# LacewingPXE_v3p1.net
KiCad netlist of a schematic drawn in Altium Designer
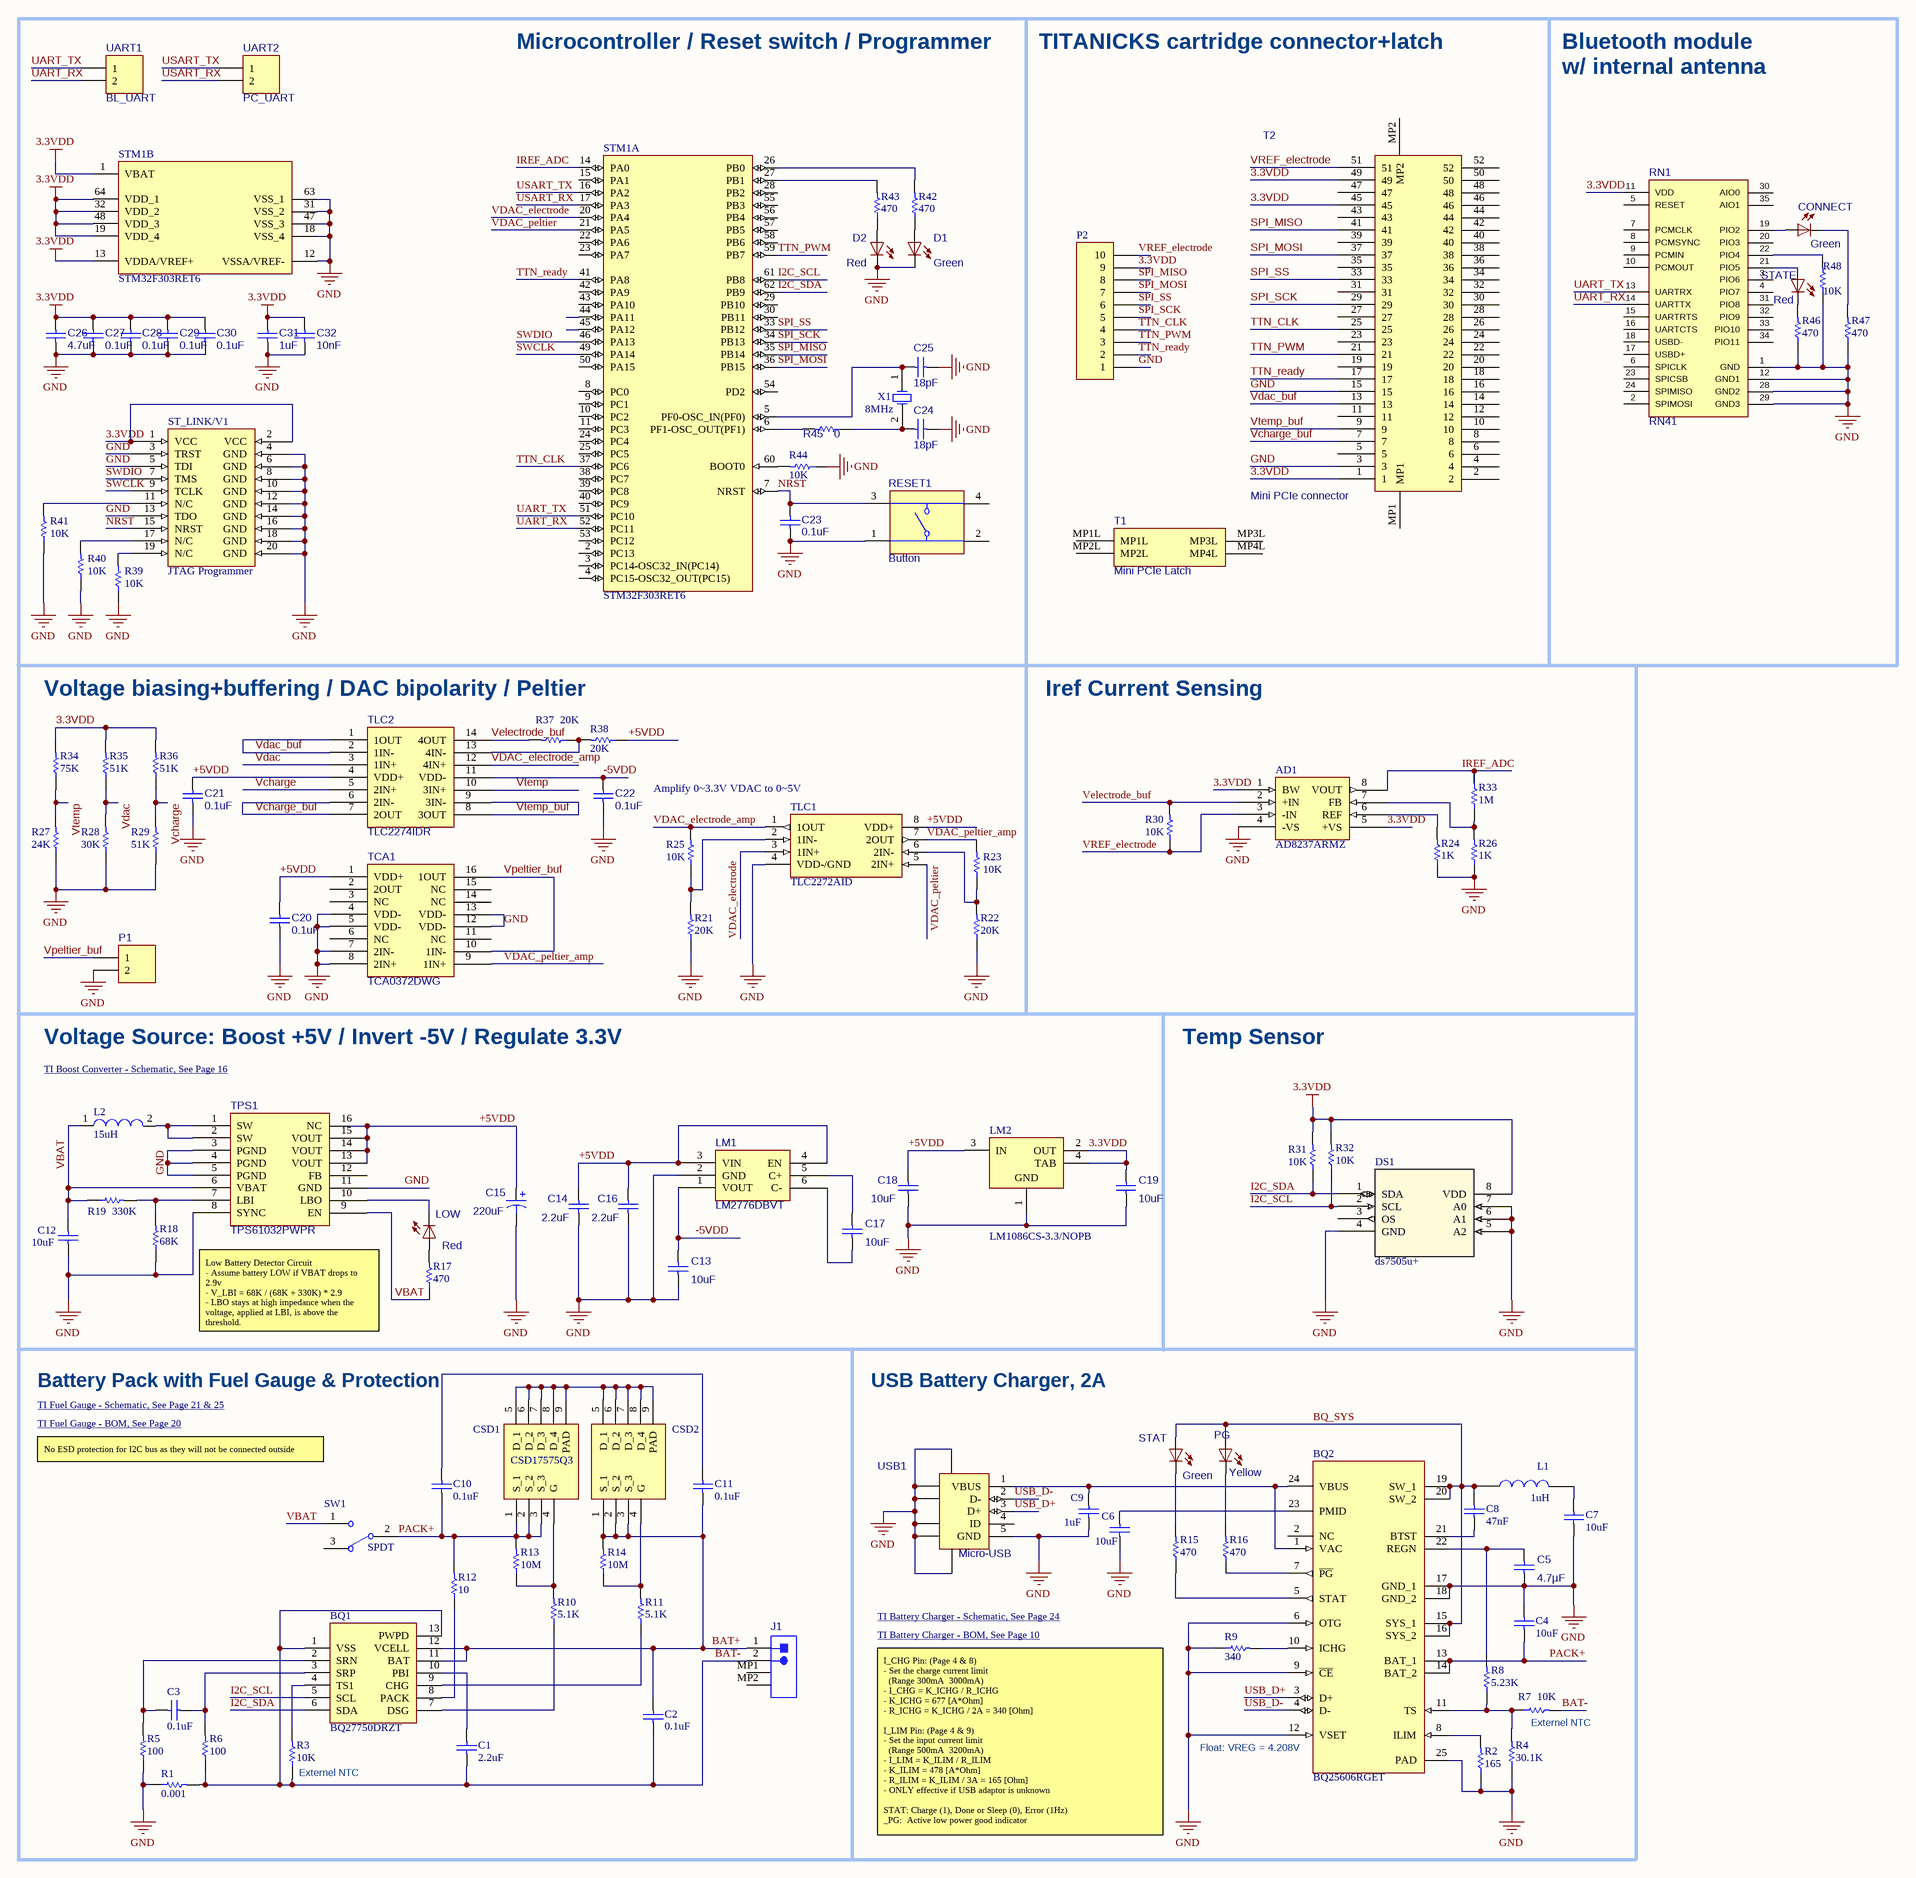
[diagram p0: LacewingPXE_v3p1.SchDoc]

(export (version "E")
  (design (tool "Eeschema 10.0.6"))
  (components
    (comp (ref "AD1")
      (value "AD8237ARMZ")
      (footprint "ADI-RM-8_N")
      (description "Instrument Amplifier")
      (fields (field (name "MANUFACTURER") "ANALOG DEVICES"))
      (libsource (lib "Device_mbd_v1") (part "AD8237"))
    )
    (comp (ref "BQ1")
      (value "BQ27750DRZT")
      (footprint "BQ27510DRZT")
      (description "Fuel Gauge and Protection")
      (fields (field (name "MANUFACTURER") "TEXAS INSTRUMENTS"))
      (libsource (lib "*") (part "BQ27750DRZT"))
    )
    (comp (ref "BQ2")
      (value "BQ25606RGET")
      (footprint "SamacSys:QFN50P400X400X100-25N")
      (description "Battery Charger")
      (fields (field (name "MANUFACTURER") "TEXAS INSTRUMENTS"))
      (libsource (lib "*") (part "BQ25606RGET"))
    )
    (comp (ref "C1")
      (value "2.2uF")
      (footprint "CAPC1005X55X25NL05T10")
      (description "CAP 0402")
      (fields (field (name "MANUFACTURER") "MURATA") (field (name "PART NO") "GRM155R60J225ME15D"))
      (libsource (lib "Altium Content Vault") (part "CAP-NP-2"))
    )
    (comp (ref "C2")
      (value "0.1uF")
      (footprint "CAPC1005X56X25LL10T15")
      (description "CAP 0402")
      (fields (field (name "MANUFACTURER") "AVX") (field (name "PART NO") "04026D104KAT2A"))
      (libsource (lib "Altium Content Vault") (part "CAP"))
    )
    (comp (ref "C3")
      (value "0.1uF")
      (footprint "CAPC1005X56X25LL10T15")
      (description "CAP 0402")
      (fields (field (name "MANUFACTURER") "AVX") (field (name "PART NO") "04026D104KAT2A"))
      (libsource (lib "Altium Content Vault") (part "CAP"))
    )
    (comp (ref "C4")
      (value "10uF")
      (footprint "CAPC2013X140X50ML20T25")
      (description "CAP 0805")
      (fields (field (name "MANUFACTURER") "AVX") (field (name "PART NO") "0805ZC106KAT2A"))
      (libsource (lib "Altium Content Vault") (part "CAP"))
    )
    (comp (ref "C5")
      (value "4.7µF")
      (footprint "CAPC0603(1608)100_N")
      (description "CAP 0603")
      (fields (field (name "MANUFACTURER") "MURATA") (field (name "PART NO") "GRM188R61C475KAAJD"))
      (libsource (lib "altium-import") (part "root_1_CAP_"))
    )
    (comp (ref "C6")
      (value "10uF")
      (footprint "CAPC2013X95X45NL10T25")
      (description "CAP 0805")
      (fields (field (name "MANUFACTURER") "MURATA") (field (name "PART NO") "GRM21BC71E106KE11L"))
      (libsource (lib "Altium Content Vault") (part "CAP"))
    )
    (comp (ref "C7")
      (value "10uF")
      (footprint "CAPC2013X140X50ML20T25")
      (description "CAP 0805")
      (fields (field (name "MANUFACTURER") "AVX") (field (name "PART NO") "0805ZC106KAT2A"))
      (libsource (lib "Altium Content Vault") (part "CAP"))
    )
    (comp (ref "C8")
      (value "47nF")
      (footprint "CAPC1005X55X25NL05T10")
      (description "CAP 0402")
      (fields (field (name "MANUFACTURER") "AVX") (field (name "PART NO") "0402YD473KAT2A"))
      (libsource (lib "Altium Content Vault") (part "CAP-NP-2"))
    )
    (comp (ref "C9")
      (value "1uF")
      (footprint "CAPC2013X95X45NL10T25")
      (description "CAP 0805")
      (fields (field (name "MANUFACTURER") "AVX") (field (name "PART NO") "08053C105JAT2A"))
      (libsource (lib "Altium Content Vault") (part "CAP"))
    )
    (comp (ref "C10")
      (value "0.1uF")
      (footprint "CAPC1005X56X25LL10T15")
      (description "CAP 0402")
      (fields (field (name "MANUFACTURER") "AVX") (field (name "PART NO") "04026D104KAT2A"))
      (libsource (lib "Altium Content Vault") (part "CAP"))
    )
    (comp (ref "C11")
      (value "0.1uF")
      (footprint "CAPC1005X56X25LL10T15")
      (description "CAP 0402")
      (fields (field (name "MANUFACTURER") "AVX") (field (name "PART NO") "04026D104KAT2A"))
      (libsource (lib "Altium Content Vault") (part "CAP"))
    )
    (comp (ref "C12")
      (value "10uF")
      (footprint "CAPC2013X140X50NL20T25")
      (description "CAP 0805")
      (fields (field (name "MANUFACTURER") "AVX") (field (name "PART NO") "08056D106KAT2A"))
      (libsource (lib "Altium Content Vault") (part "CAP"))
    )
    (comp (ref "C13")
      (value "10uF")
      (footprint "CAPC0805(2012)75_N")
      (description "CAP 0805")
      (fields (field (name "MANUFACTURER") "WURTH ELEKTRONIK") (field (name "PART NO") "885012107010"))
      (libsource (lib "Altium Content Vault") (part "CMP-1036-00002-1"))
    )
    (comp (ref "C14")
      (value "2.2uF")
      (footprint "CAPC0805(2012)75_N")
      (description "CAP 0805")
      (fields (field (name "MANUFACTURER") "MULTICOMP") (field (name "PART NO") "MC0805B225K250CT"))
      (libsource (lib "Altium Content Vault") (part "CMP-1036-00002-1"))
    )
    (comp (ref "C15")
      (value "220uF")
      (footprint "AVX-CAPC7343_V")
      (description "CAP 2917")
      (fields (field (name "MANUFACTURER") "AVX") (field (name "PART NO") "TAJD227K010RNJ"))
      (libsource (lib "Altium Content Vault") (part "CMP-0279-00002-1"))
    )
    (comp (ref "C16")
      (value "2.2uF")
      (footprint "CAPC0805(2012)75_N")
      (description "CAP 0805")
      (fields (field (name "MANUFACTURER") "MULTICOMP") (field (name "PART NO") "MC0805B225K250CT"))
      (libsource (lib "Altium Content Vault") (part "CMP-1036-00002-1"))
    )
    (comp (ref "C17")
      (value "10uF")
      (footprint "CAPC0805(2012)75_N")
      (description "CAP 0805")
      (fields (field (name "MANUFACTURER") "WURTH ELEKTRONIK") (field (name "PART NO") "885012107010"))
      (libsource (lib "Altium Content Vault") (part "CMP-1036-00002-1"))
    )
    (comp (ref "C18")
      (value "10uF")
      (footprint "CAPC0805(2012)75_N")
      (description "CAP 0805")
      (fields (field (name "MANUFACTURER") "WURTH ELEKTRONIK") (field (name "PART NO") "885012107010"))
      (libsource (lib "Altium Content Vault") (part "CMP-1036-00002-1"))
    )
    (comp (ref "C19")
      (value "10uF")
      (footprint "CAPC0805(2012)75_N")
      (description "CAP 0805")
      (fields (field (name "MANUFACTURER") "WURTH ELEKTRONIK") (field (name "PART NO") "885012107010"))
      (libsource (lib "Altium Content Vault") (part "CMP-1036-00002-1"))
    )
    (comp (ref "C20")
      (value "0.1uF")
      (footprint "CAPC0603(1608)100_N")
      (description "CAP 0603")
      (fields (field (name "MANUFACTURER") "MULTICOMP") (field (name "PART NO") "MC0603B104K500CT"))
      (libsource (lib "Altium Content Vault") (part "CAP"))
    )
    (comp (ref "C21")
      (value "0.1uF")
      (footprint "CAPC0603(1608)100_N")
      (description "CAP 0603")
      (fields (field (name "MANUFACTURER") "MULTICOMP") (field (name "PART NO") "MC0603B104K500CT"))
      (libsource (lib "Altium Content Vault") (part "CAP"))
    )
    (comp (ref "C22")
      (value "0.1uF")
      (footprint "CAPC0603(1608)100_N")
      (description "CAP 0603")
      (fields (field (name "MANUFACTURER") "MULTICOMP") (field (name "PART NO") "MC0603B104K500CT"))
      (libsource (lib "Altium Content Vault") (part "CAP"))
    )
    (comp (ref "C23")
      (value "0.1uF")
      (footprint "CAPC0603(1608)100_N")
      (description "CAP 0603")
      (fields (field (name "MANUFACTURER") "MULTICOMP") (field (name "PART NO") "MC0603B104K500CT"))
      (libsource (lib "Altium Content Vault") (part "CAP"))
    )
    (comp (ref "C24")
      (value "18pF")
      (footprint "CAPC0603(1608)100_N")
      (description "CAP 0603")
      (fields (field (name "MANUFACTURER") "KEMET") (field (name "PART NO") "C0603C180K5RACTU"))
      (libsource (lib "Altium Content Vault") (part "CAP"))
    )
    (comp (ref "C25")
      (value "18pF")
      (footprint "CAPC0603(1608)100_N")
      (description "CAP 0603")
      (fields (field (name "MANUFACTURER") "KEMET") (field (name "PART NO") "C0603C180K5RACTU"))
      (libsource (lib "Altium Content Vault") (part "CAP"))
    )
    (comp (ref "C26")
      (value "4.7uF")
      (footprint "CAPC0603(1608)100_N")
      (description "CAP 0603")
      (fields (field (name "MANUFACTURER") "AVX") (field (name "PART NO") "06036D475KAT2A"))
      (libsource (lib "Altium Content Vault") (part "CAP"))
    )
    (comp (ref "C27")
      (value "0.1uF")
      (footprint "CAPC0603(1608)100_N")
      (description "CAP 0603")
      (fields (field (name "MANUFACTURER") "MULTICOMP") (field (name "PART NO") "MC0603B104K500CT"))
      (libsource (lib "Altium Content Vault") (part "CAP"))
    )
    (comp (ref "C28")
      (value "0.1uF")
      (footprint "CAPC0603(1608)100_N")
      (description "CAP 0603")
      (fields (field (name "MANUFACTURER") "MULTICOMP") (field (name "PART NO") "MC0603B104K500CT"))
      (libsource (lib "Altium Content Vault") (part "CAP"))
    )
    (comp (ref "C29")
      (value "0.1uF")
      (footprint "CAPC0603(1608)100_N")
      (description "CAP 0603")
      (fields (field (name "MANUFACTURER") "MULTICOMP") (field (name "PART NO") "MC0603B104K500CT"))
      (libsource (lib "Altium Content Vault") (part "CAP"))
    )
    (comp (ref "C30")
      (value "0.1uF")
      (footprint "CAPC0603(1608)100_N")
      (description "CAP 0603")
      (fields (field (name "MANUFACTURER") "MULTICOMP") (field (name "PART NO") "MC0603B104K500CT"))
      (libsource (lib "Altium Content Vault") (part "CAP"))
    )
    (comp (ref "C31")
      (value "1uF")
      (footprint "CAPC0603(1608)100_N")
      (description "CAP 0603")
      (fields (field (name "MANUFACTURER") "AVX") (field (name "PART NO") "06033D105KAT2A"))
      (libsource (lib "Altium Content Vault") (part "CAP"))
    )
    (comp (ref "C32")
      (value "10nF")
      (footprint "CAPC0603(1608)100_N")
      (description "CAP 0603")
      (fields (field (name "MANUFACTURER") "KEMET") (field (name "PART NO") "C0603C103K5RAC7081"))
      (libsource (lib "Altium Content Vault") (part "CAP"))
    )
    (comp (ref "CONNECT")
      (value "Green")
      (footprint "LED-0603")
      (description "LED SMD 0603")
      (fields (field (name "MANUFACTURER") "KINGBRIGHT") (field (name "PART NO") "KPT-1608SGC"))
      (libsource (lib "TTN_chip") (part "LED0603"))
    )
    (comp (ref "CSD1")
      (value "CSD17575Q3")
      (footprint "SamacSys:CSD16327")
      (description "MOSFET")
      (fields (field (name "MANUFACTURER") "TEXAS INSTRUMENTS") (field (name "PART NO") "CSD17575Q3T"))
      (libsource (lib "*") (part "CSD17575Q3"))
    )
    (comp (ref "CSD2")
      (value "CSD17575Q3")
      (footprint "SamacSys:CSD16327")
      (description "MOSFET")
      (fields (field (name "MANUFACTURER") "TEXAS INSTRUMENTS") (field (name "PART NO") "CSD17575Q3T"))
      (libsource (lib "*") (part "CSD17575Q3"))
    )
    (comp (ref "D1")
      (value "Green")
      (footprint "LED-0603")
      (description "LED SMD 0603")
      (fields (field (name "MANUFACTURER") "KINGBRIGHT") (field (name "PART NO") "KPT-1608SGC"))
      (libsource (lib "TTN_chip") (part "LED0603"))
    )
    (comp (ref "D2")
      (value "Red")
      (footprint "LED-0603")
      (description "LED SMD 0603")
      (fields (field (name "MANUFACTURER") "KINGBRIGHT") (field (name "PART NO") "KPT-1608SECK-J3"))
      (libsource (lib "TTN_chip") (part "LED0603"))
    )
    (comp (ref "DS1")
      (value "ds7505u+")
      (footprint "21-0036K")
      (description "Digital Thermometer")
      (fields (field (name "MANUFACTURER") "MAXIM") (field (name "PART NO") "DS7505U+"))
      (libsource (lib "2019-05-15_15-51-07") (part "ds7505u+"))
    )
    (comp (ref "J1")
      (value "~")
      (footprint "JST- S2B-PH-SM4-TB(LF)(SN)-2_V")
      (description "Battery Connector")
      (fields (field (name "MANUFACTURER") "JST") (field (name "PART NO") "S2B-PH-SM4-TB(LF)(SN)"))
      (libsource (lib "Altium Content Vault") (part "SYM-0368-00001-1"))
    )
    (comp (ref "L1")
      (value "1uH")
      (footprint "INDC2520X120N")
      (description "Inductor")
      (fields (field (name "MANUFACTURER") "MURATA") (field (name "PART NO") "DFE252012F-1R0M=P2"))
      (libsource (lib "*") (part "DFE252012F-1R0M=P2"))
    )
    (comp (ref "L2")
      (value "15uH")
      (footprint "WE-PD 1050")
      (description "Power Inductor")
      (fields (field (name "MANUFACTURER") "WURTH ELEKTRONIK") (field (name "PART NO") "7447714150"))
      (libsource (lib "Altium Content Vault") (part "PAS-IND-INDUCTOR-2"))
    )
    (comp (ref "LM1")
      (value "LM2776DBVT")
      (footprint "TI-DBV6_M")
      (description "Voltage Inverter -5V")
      (fields (field (name "MANUFACTURER") "TEXAS INSTRUMENTS"))
      (libsource (lib "Device_mbd_v1") (part "LM2776"))
    )
    (comp (ref "LM2")
      (value "LM1086CS-3.3/NOPB")
      (footprint "KTT0003B_N")
      (description "1.5A 3.3V LDO")
      (fields (field (name "MANUFACTURER") "TEXAS INSTRUMENTS"))
      (libsource (lib "Altium Content Vault") (part "PM-REG-LM1086-SOT4"))
    )
    (comp (ref "LOW")
      (value "Red")
      (footprint "LED-0603")
      (description "LED SMD 0603")
      (fields (field (name "MANUFACTURER") "KINGBRIGHT") (field (name "PART NO") "KPT-1608SECK-J3"))
      (libsource (lib "TTN_chip") (part "LED0603"))
    )
    (comp (ref "P1")
      (value "~")
      (footprint "HDR1X2")
      (description "Header, 2-Pin")
      (libsource (lib "Miscellaneous Connectors") (part "Header 2"))
    )
    (comp (ref "P2")
      (value "~")
      (footprint "HDR1X10")
      (description "Header, 10-Pin")
      (libsource (lib "Miscellaneous Connectors") (part "Header 10"))
    )
    (comp (ref "PG")
      (value "Yellow")
      (footprint "LED-0603")
      (description "LED SMD 0603")
      (fields (field (name "MANUFACTURER") "KINGBRIGHT") (field (name "PART NO") "KPT-1608SYCK-J3"))
      (libsource (lib "TTN_chip") (part "LED0603"))
    )
    (comp (ref "R1")
      (value "0.001")
      (footprint "RESC3216X89X104LL25T25")
      (description "RES 1206")
      (fields (field (name "MANUFACTURER") "VISHAY") (field (name "PART NO") "WSLP12061L000FEA"))
      (libsource (lib "Altium Content Vault") (part "RES-2"))
    )
    (comp (ref "R2")
      (value "165")
      (footprint "RESC1005X40X25NL05T05")
      (description "RES 0402")
      (fields (field (name "MANUFACTURER") "VISHAY") (field (name "PART NO") "CRCW0402165RFKED"))
      (libsource (lib "Altium Content Vault") (part "RES"))
    )
    (comp (ref "R3")
      (value "10K")
      (footprint "RESC1005X40X25LL05T05")
      (description "Thermistor RES 0402")
      (fields (field (name "MANUFACTURER") "PANASONIC") (field (name "PART NO") "ERTJ0EG103FA"))
      (libsource (lib "Altium Content Vault") (part "RES"))
    )
    (comp (ref "R4")
      (value "30.1K")
      (footprint "RESC1005X40X25LL05T05")
      (description "RES 0402")
      (fields (field (name "MANUFACTURER") "VISHAY") (field (name "PART NO") "CRCW040230K1FKED"))
      (libsource (lib "Altium Content Vault") (part "RES-2"))
    )
    (comp (ref "R5")
      (value "100")
      (footprint "RESC1005X40X25NL05T05")
      (description "RES 0402")
      (fields (field (name "MANUFACTURER") "VISHAY") (field (name "PART NO") "CRCW0402100RFKED"))
      (libsource (lib "Altium Content Vault") (part "RES"))
    )
    (comp (ref "R6")
      (value "100")
      (footprint "RESC1005X40X25NL05T05")
      (description "RES 0402")
      (fields (field (name "MANUFACTURER") "VISHAY") (field (name "PART NO") "CRCW0402100RFKED"))
      (libsource (lib "Altium Content Vault") (part "RES"))
    )
    (comp (ref "R7")
      (value "10K")
      (footprint "RESC1005X40X25LL05T05")
      (description "Thermistor RES 0402")
      (fields (field (name "MANUFACTURER") "PANASONIC") (field (name "PART NO") "ERTJ0EG103FA"))
      (libsource (lib "Altium Content Vault") (part "RES"))
    )
    (comp (ref "R8")
      (value "5.23K")
      (footprint "RESC1005X40X25LL05T05")
      (description "RES 0402")
      (fields (field (name "MANUFACTURER") "VISHAY") (field (name "PART NO") "CRCW04025K23FKED"))
      (libsource (lib "Altium Content Vault") (part "RES-2"))
    )
    (comp (ref "R9")
      (value "340")
      (footprint "RESC1005X40X25LL05T05")
      (description "RES 0402")
      (fields (field (name "MANUFACTURER") "PANASONIC") (field (name "PART NO") "ERJ2RKF3400X"))
      (libsource (lib "Altium Content Vault") (part "RES"))
    )
    (comp (ref "R10")
      (value "5.1K")
      (footprint "RESC0402(1005)_N")
      (description "RES 0402")
      (fields (field (name "MANUFACTURER") "VISHAY") (field (name "PART NO") "CRCW04025K10FKED"))
      (libsource (lib "Altium Content Vault") (part "RES"))
    )
    (comp (ref "R11")
      (value "5.1K")
      (footprint "RESC0402(1005)_N")
      (description "RES 0402")
      (fields (field (name "MANUFACTURER") "VISHAY") (field (name "PART NO") "CRCW04025K10FKED"))
      (libsource (lib "Altium Content Vault") (part "RES"))
    )
    (comp (ref "R12")
      (value "10")
      (footprint "RESC1005X40X25NL05T05")
      (description "RES 0402")
      (fields (field (name "MANUFACTURER") "VISHAY") (field (name "PART NO") "CRCW040210R0FKED"))
      (libsource (lib "Altium Content Vault") (part "RES"))
    )
    (comp (ref "R13")
      (value "10M")
      (footprint "RESC1005X40X25LL05T05")
      (description "RES 0402")
      (fields (field (name "MANUFACTURER") "VISHAY") (field (name "PART NO") "CRCW040210M0FKED"))
      (libsource (lib "Altium Content Vault") (part "RES"))
    )
    (comp (ref "R14")
      (value "10M")
      (footprint "RESC1005X40X25LL05T05")
      (description "RES 0402")
      (fields (field (name "MANUFACTURER") "VISHAY") (field (name "PART NO") "CRCW040210M0FKED"))
      (libsource (lib "Altium Content Vault") (part "RES"))
    )
    (comp (ref "R15")
      (value "470")
      (footprint "RESC1005X40X25LL05T05")
      (description "RES 0402")
      (fields (field (name "MANUFACTURER") "VISHAY") (field (name "PART NO") "CRCW0402470RFKED"))
      (libsource (lib "Altium Content Vault") (part "RES"))
    )
    (comp (ref "R16")
      (value "470")
      (footprint "RESC1005X40X25LL05T05")
      (description "RES 0402")
      (fields (field (name "MANUFACTURER") "VISHAY") (field (name "PART NO") "CRCW0402470RFKED"))
      (libsource (lib "Altium Content Vault") (part "RES"))
    )
    (comp (ref "R17")
      (value "470")
      (footprint "RESC1005X40X25LL05T05")
      (description "RES 0402")
      (fields (field (name "MANUFACTURER") "VISHAY") (field (name "PART NO") "CRCW0402470RFKED"))
      (libsource (lib "Altium Content Vault") (part "RES"))
    )
    (comp (ref "R18")
      (value "68K")
      (footprint "RESC1005X40X25ML05T05")
      (description "RES 0402")
      (fields (field (name "MANUFACTURER") "VISHAY") (field (name "PART NO") "CRCW040268K0FKED"))
      (libsource (lib "Altium Content Vault") (part "RES"))
    )
    (comp (ref "R19")
      (value "330K")
      (footprint "RESC1005X40X25NL05T05")
      (description "RES 0402")
      (fields (field (name "MANUFACTURER") "VISHAY") (field (name "PART NO") "CRCW0402330KFKED"))
      (libsource (lib "Altium Content Vault") (part "RES"))
    )
    (comp (ref "R21")
      (value "20K")
      (footprint "RESC1005X40X25NL05T05")
      (description "RES 0402")
      (fields (field (name "MANUFACTURER") "VISHAY") (field (name "PART NO") "CRCW040220K0FKED"))
      (libsource (lib "Altium Content Vault") (part "RES"))
    )
    (comp (ref "R22")
      (value "20K")
      (footprint "RESC1005X40X25NL05T05")
      (description "RES 0402")
      (fields (field (name "MANUFACTURER") "VISHAY") (field (name "PART NO") "CRCW040220K0FKED"))
      (libsource (lib "Altium Content Vault") (part "RES"))
    )
    (comp (ref "R23")
      (value "10K")
      (footprint "RESC1005X40X25NL05T05")
      (description "RES 0402")
      (fields (field (name "MANUFACTURER") "VISHAY") (field (name "PART NO") "CRCW040210K0FKED"))
      (libsource (lib "Altium Content Vault") (part "RES"))
    )
    (comp (ref "R24")
      (value "1K")
      (footprint "RESC1005X40X25NL05T05")
      (description "RES 0402")
      (fields (field (name "MANUFACTURER") "VISHAY") (field (name "PART NO") "CRCW04021K00FKED"))
      (libsource (lib "Altium Content Vault") (part "RES"))
    )
    (comp (ref "R25")
      (value "10K")
      (footprint "RESC1005X40X25NL05T05")
      (description "RES 0402")
      (fields (field (name "MANUFACTURER") "VISHAY") (field (name "PART NO") "CRCW040210K0FKED"))
      (libsource (lib "Altium Content Vault") (part "RES"))
    )
    (comp (ref "R26")
      (value "1K")
      (footprint "RESC1005X40X25NL05T05")
      (description "RES 0402")
      (fields (field (name "MANUFACTURER") "VISHAY") (field (name "PART NO") "CRCW04021K00FKED"))
      (libsource (lib "Altium Content Vault") (part "RES"))
    )
    (comp (ref "R27")
      (value "24K")
      (footprint "RESC1005X40X25ML05T05")
      (description "RES 0402")
      (fields (field (name "MANUFACTURER") "VISHAY") (field (name "PART NO") "CRCW040224K0FKED"))
      (libsource (lib "Altium Content Vault") (part "RES"))
    )
    (comp (ref "R28")
      (value "30K")
      (footprint "RESC1005X40X25LL05T05")
      (description "RES 0402")
      (fields (field (name "MANUFACTURER") "VISHAY") (field (name "PART NO") "CRCW040230K0FKED"))
      (libsource (lib "Altium Content Vault") (part "RES"))
    )
    (comp (ref "R29")
      (value "51K")
      (footprint "RESC1005X40X25ML05T05")
      (description "RES 0402")
      (fields (field (name "MANUFACTURER") "VISHAY") (field (name "PART NO") "CRCW040251K0FKED"))
      (libsource (lib "Altium Content Vault") (part "RES"))
    )
    (comp (ref "R30")
      (value "10K")
      (footprint "RESC1005X40X25NL05T05")
      (description "RES 0402")
      (fields (field (name "MANUFACTURER") "VISHAY") (field (name "PART NO") "CRCW040210K0FKED"))
      (libsource (lib "Altium Content Vault") (part "RES"))
    )
    (comp (ref "R31")
      (value "10K")
      (footprint "RESC1005X40X25NL05T05")
      (description "RES 0402")
      (fields (field (name "MANUFACTURER") "VISHAY") (field (name "PART NO") "CRCW040210K0FKED"))
      (libsource (lib "Altium Content Vault") (part "RES"))
    )
    (comp (ref "R32")
      (value "10K")
      (footprint "RESC1005X40X25NL05T05")
      (description "RES 0402")
      (fields (field (name "MANUFACTURER") "VISHAY") (field (name "PART NO") "CRCW040210K0FKED"))
      (libsource (lib "Altium Content Vault") (part "RES"))
    )
    (comp (ref "R33")
      (value "1M")
      (footprint "RESC1005X40X25NL05T05")
      (description "RES 0402")
      (fields (field (name "MANUFACTURER") "VISHAY") (field (name "PART NO") "CRCW04021M00FKED"))
      (libsource (lib "Altium Content Vault") (part "RES"))
    )
    (comp (ref "R34")
      (value "75K")
      (footprint "RESC1005X40X25LL05T05")
      (description "RES 0402")
      (fields (field (name "MANUFACTURER") "VISHAY") (field (name "PART NO") "CRCW040275K0FKED"))
      (libsource (lib "Altium Content Vault") (part "RES"))
    )
    (comp (ref "R35")
      (value "51K")
      (footprint "RESC1005X40X25ML05T05")
      (description "RES 0402")
      (fields (field (name "MANUFACTURER") "VISHAY") (field (name "PART NO") "CRCW040251K0FKED"))
      (libsource (lib "Altium Content Vault") (part "RES"))
    )
    (comp (ref "R36")
      (value "51K")
      (footprint "RESC1005X40X25ML05T05")
      (description "RES 0402")
      (fields (field (name "MANUFACTURER") "VISHAY") (field (name "PART NO") "CRCW040251K0FKED"))
      (libsource (lib "Altium Content Vault") (part "RES"))
    )
    (comp (ref "R37")
      (value "20K")
      (footprint "RESC1005X40X25NL05T05")
      (description "RES 0402")
      (fields (field (name "MANUFACTURER") "VISHAY") (field (name "PART NO") "CRCW040220K0FKED"))
      (libsource (lib "Altium Content Vault") (part "RES"))
    )
    (comp (ref "R38")
      (value "20K")
      (footprint "RESC1005X40X25NL05T05")
      (description "RES 0402")
      (fields (field (name "MANUFACTURER") "VISHAY") (field (name "PART NO") "CRCW040220K0FKED"))
      (libsource (lib "Altium Content Vault") (part "RES"))
    )
    (comp (ref "R39")
      (value "10K")
      (footprint "RESC1005X40X25NL05T05")
      (description "RES 0402")
      (fields (field (name "MANUFACTURER") "VISHAY") (field (name "PART NO") "CRCW040210K0FKED"))
      (libsource (lib "Altium Content Vault") (part "RES"))
    )
    (comp (ref "R40")
      (value "10K")
      (footprint "RESC1005X40X25NL05T05")
      (description "RES 0402")
      (fields (field (name "MANUFACTURER") "VISHAY") (field (name "PART NO") "CRCW040210K0FKED"))
      (libsource (lib "Altium Content Vault") (part "RES"))
    )
    (comp (ref "R41")
      (value "10K")
      (footprint "RESC1005X40X25NL05T05")
      (description "RES 0402")
      (fields (field (name "MANUFACTURER") "VISHAY") (field (name "PART NO") "CRCW040210K0FKED"))
      (libsource (lib "Altium Content Vault") (part "RES"))
    )
    (comp (ref "R42")
      (value "470")
      (footprint "RESC1005X40X25LL05T05")
      (description "RES 0402")
      (fields (field (name "MANUFACTURER") "VISHAY") (field (name "PART NO") "CRCW0402470RFKED"))
      (libsource (lib "Altium Content Vault") (part "RES"))
    )
    (comp (ref "R43")
      (value "470")
      (footprint "RESC1005X40X25LL05T05")
      (description "RES 0402")
      (fields (field (name "MANUFACTURER") "VISHAY") (field (name "PART NO") "CRCW0402470RFKED"))
      (libsource (lib "Altium Content Vault") (part "RES"))
    )
    (comp (ref "R44")
      (value "10K")
      (footprint "RESC1005X40X25NL05T05")
      (description "RES 0402")
      (fields (field (name "MANUFACTURER") "VISHAY") (field (name "PART NO") "CRCW040210K0FKED"))
      (libsource (lib "Altium Content Vault") (part "RES"))
    )
    (comp (ref "R45")
      (value "0")
      (footprint "RESC0603(1608)_N")
      (description "RES 0603")
      (fields (field (name "MANUFACTURER") "MULTICOMP") (field (name "PART NO") "MC0603SAF0000T5E"))
      (libsource (lib "Altium Content Vault") (part "RES"))
    )
    (comp (ref "R46")
      (value "470")
      (footprint "RESC1005X40X25LL05T05")
      (description "RES 0402")
      (fields (field (name "MANUFACTURER") "VISHAY") (field (name "PART NO") "CRCW0402470RFKED"))
      (libsource (lib "Altium Content Vault") (part "RES"))
    )
    (comp (ref "R47")
      (value "470")
      (footprint "RESC1005X40X25LL05T05")
      (description "RES 0402")
      (fields (field (name "MANUFACTURER") "VISHAY") (field (name "PART NO") "CRCW0402470RFKED"))
      (libsource (lib "Altium Content Vault") (part "RES"))
    )
    (comp (ref "R48")
      (value "10K")
      (footprint "RESC1005X40X25NL05T05")
      (description "RES 0402")
      (fields (field (name "MANUFACTURER") "VISHAY") (field (name "PART NO") "CRCW040210K0FKED"))
      (libsource (lib "Altium Content Vault") (part "RES"))
    )
    (comp (ref "RESET1")
      (value "Button")
      (footprint "OMRON-B3F-1000-4_V")
      (fields (field (name "MANUFACTURER") "OMRON") (field (name "PART NO") "B3F-1022"))
      (libsource (lib "TTN_chip") (part "SW-SPST-4_A"))
    )
    (comp (ref "RN1")
      (value "RN41")
      (footprint "RN41")
      (description "RN41 Bluetooth Module")
      (fields (field (name "MANUFACTURER") "MICROCHIP") (field (name "PART NO") "RN41-I/RM"))
      (libsource (lib "Device_mbd_v1") (part "BLUETOOTH-RN41"))
    )
    (comp (ref "STAT")
      (value "Green")
      (footprint "LED-0603")
      (description "LED SMD 0603")
      (fields (field (name "MANUFACTURER") "KINGBRIGHT") (field (name "PART NO") "KPT-1608SGC"))
      (libsource (lib "TTN_chip") (part "LED0603"))
    )
    (comp (ref "STATE")
      (value "Red")
      (footprint "LED-0603")
      (description "LED SMD 0603")
      (fields (field (name "MANUFACTURER") "KINGBRIGHT") (field (name "PART NO") "KPT-1608SECK-J3"))
      (libsource (lib "TTN_chip") (part "LED0603"))
    )
    (comp (ref "STM1")
      (value "STM32F303RET6")
      (footprint "STM-LQFP64_V")
      (description "ARM Cortex-M4 32-bit MCU")
      (fields (field (name "MANUFACTURER") "STMICROELECTRONICS") (field (name "PART NO") "STM32F303RBT6"))
      (libsource (lib "STMicroelectronics STM32 F3 new") (part "STM32F303RBT6_1"))
    )
    (comp (ref "ST_LINK/V1")
      (value "JTAG Programmer")
      (footprint "JTAG2")
      (fields (field (name "MANUFACTURER") "AMPHENOL") (field (name "PART NO") "T821120A1S100CEU"))
      (libsource (lib "Device_mbd_v1") (part "JTAG"))
    )
    (comp (ref "SW1")
      (value "SPDT")
      (footprint "1000-SERIES(SPDT)")
      (fields (field (name "MANUFACTURER") "C & K COMPONENTS") (field (name "PART NO") "1101M1S3ZQE2"))
      (libsource (lib "*") (part "1101M1S3ZQE2"))
    )
    (comp (ref "T1")
      (value "Mini PCIe Latch")
      (footprint "Molex Latch-48099")
      (fields (field (name "MANUFACTURER") "MOLEX") (field (name "PART NO") "48099-5701"))
      (libsource (lib "Device_mbd_v1") (part "Mini PCIe Latch"))
    )
    (comp (ref "T2")
      (value "Mini PCIe connector")
      (footprint "Molex Conn-67910")
      (description "Mini PCIe Connector")
      (fields (field (name "MANUFACTURER") "MOLEX") (field (name "PART NO") "67910-5700"))
      (libsource (lib "Device_mbd_v1") (part "Mini PCIe connector"))
    )
    (comp (ref "TCA1")
      (value "TCA0372DWG")
      (footprint "ONSC-SOIC-16-751G-03_V")
      (description "Dual High-Power OPAMP")
      (fields (field (name "MANUFACTURER") "ON SEMICONDUCTOR"))
      (libsource (lib "TTN_chip") (part "TCA0372"))
    )
    (comp (ref "TLC1")
      (value "TLC2272AID")
      (footprint "SOIC127P600X175-8N")
      (description "Dual OPAMP")
      (fields (field (name "MANUFACTURER") "TEXAS INSTRUMENTS"))
      (libsource (lib "*") (part "TLC2272AID"))
    )
    (comp (ref "TLC2")
      (value "TLC2274IDR")
      (footprint "TI-D14_M")
      (description "Quad OPAMP")
      (fields (field (name "MANUFACTURER") "TEXAS INSTRUMENTS"))
      (libsource (lib "TTN_chip") (part "TLC2274"))
    )
    (comp (ref "TPS1")
      (value "TPS61032PWPR")
      (footprint "PW0016A_M")
      (description "Voltage Boost +5V")
      (fields (field (name "MANUFACTURER") "TEXAS INSTRUMENTS"))
      (libsource (lib "TTN_chip") (part "TPS61032"))
    )
    (comp (ref "UART1")
      (value "BL_UART")
      (footprint "HDR1X2")
      (description "Header, 2-Pin")
      (fields (field (name "PUBLISHER") "Altium Limited"))
      (libsource (lib "Miscellaneous Connectors") (part "Header 2"))
    )
    (comp (ref "UART2")
      (value "PC_UART")
      (footprint "HDR1X2")
      (description "Header, 2-Pin")
      (fields (field (name "PUBLISHER") "Altium Limited"))
      (libsource (lib "Miscellaneous Connectors") (part "Header 2"))
    )
    (comp (ref "USB1")
      (value "Micro-USB")
      (footprint "HIRO-ZX62R-B-5P_V")
      (description "ZX62R-B-5P")
      (fields (field (name "MANUFACTURER") "HIROSE") (field (name "PART NO") "ZX62R-B-5P(30)"))
      (libsource (lib "Altium Content Vault") (part "HIRO-ZX62R-B-5P-5"))
    )
    (comp (ref "X1")
      (value "8MHz")
      (footprint "QCL")
      (description "Crystal Oscillator")
      (fields (field (name "MANUFACTURER") "QANTEK") (field (name "PART NO") "QCL8.00000F18B23B"))
      (libsource (lib "Miscellaneous Devices") (part "XTAL"))
    )
  )
  (nets
    (net (code "1") (name "/+5VDD") (class "Default")
      (node (ref "C14") (pin "2") (pinfunction "2_2") (pintype "passive"))
      (node (ref "C15") (pin "1") (pinfunction "1_1") (pintype "passive"))
      (node (ref "C16") (pin "2") (pinfunction "2_2") (pintype "passive"))
      (node (ref "C18") (pin "1") (pinfunction "1_1") (pintype "passive"))
      (node (ref "C20") (pin "1") (pinfunction "1_1") (pintype "passive"))
      (node (ref "C21") (pin "1") (pinfunction "1_1") (pintype "passive"))
      (node (ref "LM1") (pin "3") (pinfunction "VIN_3") (pintype "passive"))
      (node (ref "LM1") (pin "4") (pinfunction "EN_4") (pintype "passive"))
      (node (ref "LM2") (pin "3") (pinfunction "IN_3") (pintype "power_in"))
      (node (ref "R38") (pin "1") (pinfunction "1_1") (pintype "passive"))
      (node (ref "TCA1") (pin "1") (pinfunction "VDD+_1") (pintype "passive"))
      (node (ref "TLC1") (pin "8") (pinfunction "VDD+_8") (pintype "power_in"))
      (node (ref "TLC2") (pin "4") (pinfunction "VDD+_4") (pintype "passive"))
      (node (ref "TPS1") (pin "13") (pinfunction "VOUT_13") (pintype "passive"))
      (node (ref "TPS1") (pin "14") (pinfunction "VOUT_14") (pintype "passive"))
      (node (ref "TPS1") (pin "15") (pinfunction "VOUT_15") (pintype "passive"))
      (node (ref "TPS1") (pin "16") (pinfunction "NC_16") (pintype "passive"))
    )
    (net (code "2") (name "/-5VDD") (class "Default")
      (node (ref "C13") (pin "1") (pinfunction "1_1") (pintype "passive"))
      (node (ref "C22") (pin "1") (pinfunction "1_1") (pintype "passive"))
      (node (ref "LM1") (pin "1") (pinfunction "VOUT_1") (pintype "passive"))
      (node (ref "TLC2") (pin "11") (pinfunction "VDD-_11") (pintype "passive"))
    )
    (net (code "3") (name "/BAT+") (class "Default")
      (node (ref "BQ1") (pin "11") (pinfunction "BAT_11") (pintype "passive"))
      (node (ref "BQ1") (pin "12") (pinfunction "VCELL_12") (pintype "passive"))
      (node (ref "C11") (pin "1") (pinfunction "1_1") (pintype "passive"))
      (node (ref "C2") (pin "2") (pinfunction "2_2") (pintype "passive"))
      (node (ref "CSD2") (pin "1") (pinfunction "S_1_1") (pintype "passive"))
      (node (ref "CSD2") (pin "2") (pinfunction "S_2_2") (pintype "passive"))
      (node (ref "CSD2") (pin "3") (pinfunction "S_3_3") (pintype "passive"))
      (node (ref "J1") (pin "1") (pinfunction "1_1") (pintype "passive"))
      (node (ref "R14") (pin "2") (pinfunction "2_2") (pintype "passive"))
    )
    (net (code "4") (name "/BAT-") (class "Default")
      (node (ref "BQ1") (pin "1") (pinfunction "VSS_1") (pintype "passive"))
      (node (ref "BQ1") (pin "13") (pinfunction "PWPD_13") (pintype "passive"))
      (node (ref "C1") (pin "1") (pinfunction "1_1") (pintype "passive"))
      (node (ref "C2") (pin "1") (pinfunction "1_1") (pintype "passive"))
      (node (ref "J1") (pin "2") (pinfunction "2_2") (pintype "passive"))
      (node (ref "R1") (pin "2") (pinfunction "2_2") (pintype "passive"))
      (node (ref "R3") (pin "1") (pinfunction "1_1") (pintype "passive"))
      (node (ref "R6") (pin "1") (pinfunction "1_1") (pintype "passive"))
      (node (ref "R7") (pin "2") (pinfunction "2_2") (pintype "passive"))
    )
    (net (code "5") (name "/BQ_SYS") (class "Default")
      (node (ref "BQ2") (pin "15") (pinfunction "SYS_1_15") (pintype "power_in"))
      (node (ref "BQ2") (pin "16") (pinfunction "SYS_2_16") (pintype "power_in"))
      (node (ref "BQ2") (pin "19") (pinfunction "SW_1_19") (pintype "power_in"))
      (node (ref "BQ2") (pin "20") (pinfunction "SW_2_20") (pintype "power_in"))
      (node (ref "C8") (pin "2") (pinfunction "2_2") (pintype "passive"))
      (node (ref "L1") (pin "1") (pinfunction "1_1") (pintype "passive"))
      (node (ref "PG") (pin "A") (pinfunction "A_A") (pintype "passive"))
      (node (ref "STAT") (pin "A") (pinfunction "A_A") (pintype "passive"))
    )
    (net (code "6") (name "/I2C_SCL") (class "Default")
      (node (ref "BQ1") (pin "5") (pinfunction "SCL_5") (pintype "passive"))
      (node (ref "DS1") (pin "2") (pinfunction "SCL_2") (pintype "input"))
      (node (ref "R32") (pin "1") (pinfunction "1_1") (pintype "passive"))
      (node (ref "STM1") (pin "61") (pinfunction "PB8_61") (pintype "bidirectional"))
    )
    (net (code "7") (name "/I2C_SDA") (class "Default")
      (node (ref "BQ1") (pin "6") (pinfunction "SDA_6") (pintype "passive"))
      (node (ref "DS1") (pin "1") (pinfunction "SDA_1") (pintype "bidirectional"))
      (node (ref "R31") (pin "1") (pinfunction "1_1") (pintype "passive"))
      (node (ref "STM1") (pin "62") (pinfunction "PB9_62") (pintype "bidirectional"))
    )
    (net (code "8") (name "/IREF_ADC") (class "Default")
      (node (ref "AD1") (pin "8") (pinfunction "VOUT_8") (pintype "output"))
      (node (ref "R33") (pin "2") (pinfunction "2_2") (pintype "passive"))
      (node (ref "STM1") (pin "14") (pinfunction "PA0_14") (pintype "bidirectional"))
    )
    (net (code "9") (name "/NRST") (class "Default")
      (node (ref "C23") (pin "1") (pinfunction "1_1") (pintype "passive"))
      (node (ref "RESET1") (pin "3") (pinfunction "3_3") (pintype "passive"))
      (node (ref "STM1") (pin "7") (pinfunction "NRST_7") (pintype "bidirectional"))
      (node (ref "ST_LINK/V1") (pin "15") (pinfunction "NRST_15") (pintype "input"))
    )
    (net (code "10") (name "/PACK+") (class "Default")
      (node (ref "BQ2") (pin "13") (pinfunction "BAT_1_13") (pintype "power_in"))
      (node (ref "BQ2") (pin "14") (pinfunction "BAT_2_14") (pintype "power_in"))
      (node (ref "C10") (pin "1") (pinfunction "1_1") (pintype "passive"))
      (node (ref "C4") (pin "1") (pinfunction "1_1") (pintype "passive"))
      (node (ref "CSD1") (pin "1") (pinfunction "S_1_1") (pintype "passive"))
      (node (ref "CSD1") (pin "2") (pinfunction "S_2_2") (pintype "passive"))
      (node (ref "CSD1") (pin "3") (pinfunction "S_3_3") (pintype "passive"))
      (node (ref "R12") (pin "2") (pinfunction "2_2") (pintype "passive"))
      (node (ref "R13") (pin "2") (pinfunction "2_2") (pintype "passive"))
      (node (ref "SW1") (pin "2") (pinfunction "2_2") (pintype "passive"))
    )
    (net (code "11") (name "/SPI_MISO") (class "Default")
      (node (ref "P2") (pin "8") (pinfunction "8_8") (pintype "passive"))
      (node (ref "STM1") (pin "35") (pinfunction "PB14_35") (pintype "bidirectional"))
      (node (ref "T2") (pin "41") (pinfunction "41_41") (pintype "passive"))
    )
    (net (code "12") (name "/SPI_MOSI") (class "Default")
      (node (ref "P2") (pin "7") (pinfunction "7_7") (pintype "passive"))
      (node (ref "STM1") (pin "36") (pinfunction "PB15_36") (pintype "bidirectional"))
      (node (ref "T2") (pin "37") (pinfunction "37_37") (pintype "passive"))
    )
    (net (code "13") (name "/SPI_SCK") (class "Default")
      (node (ref "P2") (pin "5") (pinfunction "5_5") (pintype "passive"))
      (node (ref "STM1") (pin "34") (pinfunction "PB13_34") (pintype "bidirectional"))
      (node (ref "T2") (pin "29") (pinfunction "29_29") (pintype "passive"))
    )
    (net (code "14") (name "/SPI_SS") (class "Default")
      (node (ref "P2") (pin "6") (pinfunction "6_6") (pintype "passive"))
      (node (ref "STM1") (pin "33") (pinfunction "PB12_33") (pintype "bidirectional"))
      (node (ref "T2") (pin "33") (pinfunction "33_33") (pintype "passive"))
    )
    (net (code "15") (name "/SWCLK") (class "Default")
      (node (ref "STM1") (pin "49") (pinfunction "PA14_49") (pintype "bidirectional"))
      (node (ref "ST_LINK/V1") (pin "9") (pinfunction "TCLK_9") (pintype "input"))
    )
    (net (code "16") (name "/SWDIO") (class "Default")
      (node (ref "STM1") (pin "46") (pinfunction "PA13_46") (pintype "bidirectional"))
      (node (ref "ST_LINK/V1") (pin "7") (pinfunction "TMS_7") (pintype "input"))
    )
    (net (code "17") (name "/TTN_CLK") (class "Default")
      (node (ref "P2") (pin "4") (pinfunction "4_4") (pintype "passive"))
      (node (ref "STM1") (pin "37") (pinfunction "PC6_37") (pintype "bidirectional"))
      (node (ref "T2") (pin "25") (pinfunction "25_25") (pintype "passive"))
    )
    (net (code "18") (name "/TTN_PWM") (class "Default")
      (node (ref "P2") (pin "3") (pinfunction "3_3") (pintype "passive"))
      (node (ref "STM1") (pin "59") (pinfunction "PB7_59") (pintype "bidirectional"))
      (node (ref "T2") (pin "21") (pinfunction "21_21") (pintype "passive"))
    )
    (net (code "19") (name "/TTN_ready") (class "Default")
      (node (ref "P2") (pin "2") (pinfunction "2_2") (pintype "passive"))
      (node (ref "STM1") (pin "41") (pinfunction "PA8_41") (pintype "bidirectional"))
      (node (ref "T2") (pin "17") (pinfunction "17_17") (pintype "passive"))
    )
    (net (code "20") (name "/UART_RX") (class "Default")
      (node (ref "RN1") (pin "14") (pinfunction "UARTTX_14") (pintype "passive"))
      (node (ref "STM1") (pin "52") (pinfunction "PC11_52") (pintype "bidirectional"))
      (node (ref "UART1") (pin "2") (pinfunction "2_2") (pintype "passive"))
    )
    (net (code "21") (name "/UART_TX") (class "Default")
      (node (ref "RN1") (pin "13") (pinfunction "UARTRX_13") (pintype "passive"))
      (node (ref "STM1") (pin "51") (pinfunction "PC10_51") (pintype "bidirectional"))
      (node (ref "UART1") (pin "1") (pinfunction "1_1") (pintype "passive"))
    )
    (net (code "22") (name "/USART_RX") (class "Default")
      (node (ref "STM1") (pin "17") (pinfunction "PA3_17") (pintype "bidirectional"))
      (node (ref "UART2") (pin "2") (pinfunction "2_2") (pintype "passive"))
    )
    (net (code "23") (name "/USART_TX") (class "Default")
      (node (ref "STM1") (pin "16") (pinfunction "PA2_16") (pintype "bidirectional"))
      (node (ref "UART2") (pin "1") (pinfunction "1_1") (pintype "passive"))
    )
    (net (code "24") (name "/USB_D+") (class "Default")
      (node (ref "BQ2") (pin "3") (pinfunction "D+_3") (pintype "bidirectional"))
      (node (ref "USB1") (pin "3") (pinfunction "D+_3") (pintype "bidirectional"))
    )
    (net (code "25") (name "/USB_D-") (class "Default")
      (node (ref "BQ2") (pin "4") (pinfunction "D-_4") (pintype "bidirectional"))
      (node (ref "USB1") (pin "2") (pinfunction "D-_2") (pintype "bidirectional"))
    )
    (net (code "26") (name "/VBAT") (class "Default")
      (node (ref "C12") (pin "2") (pinfunction "2_2") (pintype "passive"))
      (node (ref "L2") (pin "1") (pinfunction "1_1") (pintype "passive"))
      (node (ref "R17") (pin "1") (pinfunction "1_1") (pintype "passive"))
      (node (ref "R19") (pin "1") (pinfunction "1_1") (pintype "passive"))
      (node (ref "SW1") (pin "1") (pinfunction "1_1") (pintype "passive"))
      (node (ref "TPS1") (pin "6") (pinfunction "VBAT_6") (pintype "passive"))
      (node (ref "TPS1") (pin "9") (pinfunction "EN_9") (pintype "passive"))
    )
    (net (code "27") (name "/VDAC_electrode") (class "Default")
      (node (ref "STM1") (pin "20") (pinfunction "PA4_20") (pintype "bidirectional"))
      (node (ref "TLC1") (pin "3") (pinfunction "1IN+_3") (pintype "input"))
    )
    (net (code "28") (name "/VDAC_electrode_amp") (class "Default")
      (node (ref "R25") (pin "2") (pinfunction "2_2") (pintype "passive"))
      (node (ref "TLC1") (pin "1") (pinfunction "1OUT_1") (pintype "output"))
      (node (ref "TLC2") (pin "12") (pinfunction "4IN+_12") (pintype "passive"))
    )
    (net (code "29") (name "/VDAC_peltier") (class "Default")
      (node (ref "STM1") (pin "21") (pinfunction "PA5_21") (pintype "bidirectional"))
      (node (ref "TLC1") (pin "5") (pinfunction "2IN+_5") (pintype "input"))
    )
    (net (code "30") (name "/VDAC_peltier_amp") (class "Default")
      (node (ref "R23") (pin "2") (pinfunction "2_2") (pintype "passive"))
      (node (ref "TCA1") (pin "9") (pinfunction "1IN+_9") (pintype "passive"))
      (node (ref "TLC1") (pin "7") (pinfunction "2OUT_7") (pintype "output"))
    )
    (net (code "31") (name "/VREF_electrode") (class "Default")
      (node (ref "AD1") (pin "3") (pinfunction "-IN_3") (pintype "input"))
      (node (ref "P2") (pin "10") (pinfunction "10_10") (pintype "passive"))
      (node (ref "R30") (pin "1") (pinfunction "1_1") (pintype "passive"))
      (node (ref "T2") (pin "51") (pinfunction "51_51") (pintype "passive"))
    )
    (net (code "32") (name "/Vcharge") (class "Default")
      (node (ref "R29") (pin "2") (pinfunction "2_2") (pintype "passive"))
      (node (ref "R36") (pin "1") (pinfunction "1_1") (pintype "passive"))
      (node (ref "TLC2") (pin "5") (pinfunction "2IN+_5") (pintype "passive"))
    )
    (net (code "33") (name "/Vcharge_buf") (class "Default")
      (node (ref "T2") (pin "7") (pinfunction "7_7") (pintype "passive"))
      (node (ref "TLC2") (pin "6") (pinfunction "2IN-_6") (pintype "passive"))
      (node (ref "TLC2") (pin "7") (pinfunction "2OUT_7") (pintype "passive"))
    )
    (net (code "34") (name "/Vdac") (class "Default")
      (node (ref "R28") (pin "2") (pinfunction "2_2") (pintype "passive"))
      (node (ref "R35") (pin "1") (pinfunction "1_1") (pintype "passive"))
      (node (ref "TLC2") (pin "3") (pinfunction "1IN+_3") (pintype "passive"))
    )
    (net (code "35") (name "/Vdac_buf") (class "Default")
      (node (ref "T2") (pin "13") (pinfunction "13_13") (pintype "passive"))
      (node (ref "TLC2") (pin "1") (pinfunction "1OUT_1") (pintype "passive"))
      (node (ref "TLC2") (pin "2") (pinfunction "1IN-_2") (pintype "passive"))
    )
    (net (code "36") (name "/Velectrode_buf") (class "Default")
      (node (ref "AD1") (pin "2") (pinfunction "+IN_2") (pintype "input"))
      (node (ref "R30") (pin "2") (pinfunction "2_2") (pintype "passive"))
      (node (ref "R37") (pin "2") (pinfunction "2_2") (pintype "passive"))
      (node (ref "TLC2") (pin "14") (pinfunction "4OUT_14") (pintype "passive"))
    )
    (net (code "37") (name "/Vpeltier_buf") (class "Default")
      (node (ref "P1") (pin "1") (pinfunction "1_1") (pintype "passive"))
      (node (ref "TCA1") (pin "10") (pinfunction "1IN-_10") (pintype "passive"))
      (node (ref "TCA1") (pin "16") (pinfunction "1OUT_16") (pintype "passive"))
    )
    (net (code "38") (name "/Vtemp") (class "Default")
      (node (ref "R27") (pin "2") (pinfunction "2_2") (pintype "passive"))
      (node (ref "R34") (pin "1") (pinfunction "1_1") (pintype "passive"))
      (node (ref "TLC2") (pin "10") (pinfunction "3IN+_10") (pintype "passive"))
    )
    (net (code "39") (name "/Vtemp_buf") (class "Default")
      (node (ref "T2") (pin "9") (pinfunction "9_9") (pintype "passive"))
      (node (ref "TLC2") (pin "8") (pinfunction "3OUT_8") (pintype "passive"))
      (node (ref "TLC2") (pin "9") (pinfunction "3IN-_9") (pintype "passive"))
    )
    (net (code "40") (name "3.3VDD") (class "Default")
      (node (ref "AD1") (pin "1") (pinfunction "BW_1") (pintype "input"))
      (node (ref "AD1") (pin "5") (pinfunction "+VS_5") (pintype "power_in"))
      (node (ref "C19") (pin "1") (pinfunction "1_1") (pintype "passive"))
      (node (ref "C26") (pin "1") (pinfunction "1_1") (pintype "passive"))
      (node (ref "C27") (pin "1") (pinfunction "1_1") (pintype "passive"))
      (node (ref "C28") (pin "1") (pinfunction "1_1") (pintype "passive"))
      (node (ref "C29") (pin "1") (pinfunction "1_1") (pintype "passive"))
      (node (ref "C30") (pin "1") (pinfunction "1_1") (pintype "passive"))
      (node (ref "C31") (pin "1") (pinfunction "1_1") (pintype "passive"))
      (node (ref "C32") (pin "1") (pinfunction "1_1") (pintype "passive"))
      (node (ref "DS1") (pin "8") (pinfunction "VDD_8") (pintype "power_in"))
      (node (ref "LM2") (pin "2") (pinfunction "OUT_2") (pintype "power_in"))
      (node (ref "LM2") (pin "4") (pinfunction "TAB_4") (pintype "power_in"))
      (node (ref "P2") (pin "9") (pinfunction "9_9") (pintype "passive"))
      (node (ref "R31") (pin "2") (pinfunction "2_2") (pintype "passive"))
      (node (ref "R32") (pin "2") (pinfunction "2_2") (pintype "passive"))
      (node (ref "R34") (pin "2") (pinfunction "2_2") (pintype "passive"))
      (node (ref "R35") (pin "2") (pinfunction "2_2") (pintype "passive"))
      (node (ref "R36") (pin "2") (pinfunction "2_2") (pintype "passive"))
      (node (ref "RN1") (pin "11") (pinfunction "VDD_11") (pintype "passive"))
      (node (ref "STM1") (pin "1") (pinfunction "VBAT_1") (pintype "power_in"))
      (node (ref "STM1") (pin "13") (pinfunction "VDDA/VREF+_13") (pintype "power_in"))
      (node (ref "STM1") (pin "19") (pinfunction "VDD_4_19") (pintype "power_in"))
      (node (ref "STM1") (pin "32") (pinfunction "VDD_2_32") (pintype "power_in"))
      (node (ref "STM1") (pin "48") (pinfunction "VDD_3_48") (pintype "power_in"))
      (node (ref "STM1") (pin "64") (pinfunction "VDD_1_64") (pintype "power_in"))
      (node (ref "ST_LINK/V1") (pin "1") (pinfunction "VCC_1") (pintype "input"))
      (node (ref "ST_LINK/V1") (pin "2") (pinfunction "VCC_2") (pintype "input"))
      (node (ref "T2") (pin "1") (pinfunction "1_1") (pintype "passive"))
      (node (ref "T2") (pin "45") (pinfunction "45_45") (pintype "passive"))
      (node (ref "T2") (pin "49") (pinfunction "49_49") (pintype "passive"))
    )
    (net (code "41") (name "GND") (class "Default")
      (node (ref "AD1") (pin "4") (pinfunction "-VS_4") (pintype "power_in"))
      (node (ref "BQ2") (pin "12") (pinfunction "VSET_12") (pintype "input"))
      (node (ref "BQ2") (pin "17") (pinfunction "GND_1_17") (pintype "power_in"))
      (node (ref "BQ2") (pin "18") (pinfunction "GND_2_18") (pintype "power_in"))
      (node (ref "BQ2") (pin "25") (pinfunction "PAD_25") (pintype "power_in"))
      (node (ref "BQ2") (pin "6") (pinfunction "OTG_6") (pintype "input"))
      (node (ref "BQ2") (pin "9") (pinfunction "~{CE}_9") (pintype "input"))
      (node (ref "C12") (pin "1") (pinfunction "1_1") (pintype "passive"))
      (node (ref "C13") (pin "2") (pinfunction "2_2") (pintype "passive"))
      (node (ref "C14") (pin "1") (pinfunction "1_1") (pintype "passive"))
      (node (ref "C15") (pin "2") (pinfunction "2_2") (pintype "passive"))
      (node (ref "C16") (pin "1") (pinfunction "1_1") (pintype "passive"))
      (node (ref "C18") (pin "2") (pinfunction "2_2") (pintype "passive"))
      (node (ref "C19") (pin "2") (pinfunction "2_2") (pintype "passive"))
      (node (ref "C20") (pin "2") (pinfunction "2_2") (pintype "passive"))
      (node (ref "C21") (pin "2") (pinfunction "2_2") (pintype "passive"))
      (node (ref "C22") (pin "2") (pinfunction "2_2") (pintype "passive"))
      (node (ref "C23") (pin "2") (pinfunction "2_2") (pintype "passive"))
      (node (ref "C24") (pin "2") (pinfunction "2_2") (pintype "passive"))
      (node (ref "C25") (pin "2") (pinfunction "2_2") (pintype "passive"))
      (node (ref "C26") (pin "2") (pinfunction "2_2") (pintype "passive"))
      (node (ref "C27") (pin "2") (pinfunction "2_2") (pintype "passive"))
      (node (ref "C28") (pin "2") (pinfunction "2_2") (pintype "passive"))
      (node (ref "C29") (pin "2") (pinfunction "2_2") (pintype "passive"))
      (node (ref "C30") (pin "2") (pinfunction "2_2") (pintype "passive"))
      (node (ref "C31") (pin "2") (pinfunction "2_2") (pintype "passive"))
      (node (ref "C32") (pin "2") (pinfunction "2_2") (pintype "passive"))
      (node (ref "C4") (pin "2") (pinfunction "2_2") (pintype "passive"))
      (node (ref "C5") (pin "1") (pinfunction "1_1") (pintype "passive"))
      (node (ref "C6") (pin "1") (pinfunction "1_1") (pintype "passive"))
      (node (ref "C7") (pin "1") (pinfunction "1_1") (pintype "passive"))
      (node (ref "C9") (pin "1") (pinfunction "1_1") (pintype "passive"))
      (node (ref "D1") (pin "C") (pinfunction "C_C") (pintype "passive"))
      (node (ref "D2") (pin "C") (pinfunction "C_C") (pintype "passive"))
      (node (ref "DS1") (pin "4") (pinfunction "GND_4") (pintype "power_in"))
      (node (ref "DS1") (pin "5") (pinfunction "A2_5") (pintype "input"))
      (node (ref "DS1") (pin "6") (pinfunction "A1_6") (pintype "input"))
      (node (ref "DS1") (pin "7") (pinfunction "A0_7") (pintype "input"))
      (node (ref "LM1") (pin "2") (pinfunction "GND_2") (pintype "passive"))
      (node (ref "LM2") (pin "1") (pinfunction "GND_1") (pintype "power_in"))
      (node (ref "P1") (pin "2") (pinfunction "2_2") (pintype "passive"))
      (node (ref "P2") (pin "1") (pinfunction "1_1") (pintype "passive"))
      (node (ref "R1") (pin "1") (pinfunction "1_1") (pintype "passive"))
      (node (ref "R18") (pin "1") (pinfunction "1_1") (pintype "passive"))
      (node (ref "R2") (pin "1") (pinfunction "1_1") (pintype "passive"))
      (node (ref "R21") (pin "1") (pinfunction "1_1") (pintype "passive"))
      (node (ref "R22") (pin "1") (pinfunction "1_1") (pintype "passive"))
      (node (ref "R24") (pin "1") (pinfunction "1_1") (pintype "passive"))
      (node (ref "R26") (pin "1") (pinfunction "1_1") (pintype "passive"))
      (node (ref "R27") (pin "1") (pinfunction "1_1") (pintype "passive"))
      (node (ref "R28") (pin "1") (pinfunction "1_1") (pintype "passive"))
      (node (ref "R29") (pin "1") (pinfunction "1_1") (pintype "passive"))
      (node (ref "R39") (pin "1") (pinfunction "1_1") (pintype "passive"))
      (node (ref "R4") (pin "1") (pinfunction "1_1") (pintype "passive"))
      (node (ref "R40") (pin "1") (pinfunction "1_1") (pintype "passive"))
      (node (ref "R41") (pin "1") (pinfunction "1_1") (pintype "passive"))
      (node (ref "R44") (pin "1") (pinfunction "1_1") (pintype "passive"))
      (node (ref "R46") (pin "1") (pinfunction "1_1") (pintype "passive"))
      (node (ref "R47") (pin "1") (pinfunction "1_1") (pintype "passive"))
      (node (ref "R48") (pin "1") (pinfunction "1_1") (pintype "passive"))
      (node (ref "R5") (pin "1") (pinfunction "1_1") (pintype "passive"))
      (node (ref "R9") (pin "1") (pinfunction "1_1") (pintype "passive"))
      (node (ref "RESET1") (pin "1") (pinfunction "1_1") (pintype "passive"))
      (node (ref "RN1") (pin "1") (pinfunction "GND_1") (pintype "passive"))
      (node (ref "RN1") (pin "12") (pinfunction "GND1_12") (pintype "passive"))
      (node (ref "RN1") (pin "28") (pinfunction "GND2_28") (pintype "passive"))
      (node (ref "RN1") (pin "29") (pinfunction "GND3_29") (pintype "passive"))
      (node (ref "STM1") (pin "12") (pinfunction "VSSA/VREF-_12") (pintype "power_in"))
      (node (ref "STM1") (pin "18") (pinfunction "VSS_4_18") (pintype "power_in"))
      (node (ref "STM1") (pin "31") (pinfunction "VSS_2_31") (pintype "power_in"))
      (node (ref "STM1") (pin "47") (pinfunction "VSS_3_47") (pintype "power_in"))
      (node (ref "STM1") (pin "63") (pinfunction "VSS_1_63") (pintype "power_in"))
      (node (ref "ST_LINK/V1") (pin "10") (pinfunction "GND_10") (pintype "input"))
      (node (ref "ST_LINK/V1") (pin "12") (pinfunction "GND_12") (pintype "input"))
      (node (ref "ST_LINK/V1") (pin "13") (pinfunction "TDO_13") (pintype "input"))
      (node (ref "ST_LINK/V1") (pin "14") (pinfunction "GND_14") (pintype "input"))
      (node (ref "ST_LINK/V1") (pin "16") (pinfunction "GND_16") (pintype "input"))
      (node (ref "ST_LINK/V1") (pin "18") (pinfunction "GND_18") (pintype "input"))
      (node (ref "ST_LINK/V1") (pin "20") (pinfunction "GND_20") (pintype "input"))
      (node (ref "ST_LINK/V1") (pin "3") (pinfunction "TRST_3") (pintype "input"))
      (node (ref "ST_LINK/V1") (pin "4") (pinfunction "GND_4") (pintype "input"))
      (node (ref "ST_LINK/V1") (pin "5") (pinfunction "TDI_5") (pintype "input"))
      (node (ref "ST_LINK/V1") (pin "6") (pinfunction "GND_6") (pintype "input"))
      (node (ref "ST_LINK/V1") (pin "8") (pinfunction "GND_8") (pintype "input"))
      (node (ref "T2") (pin "15") (pinfunction "15_15") (pintype "passive"))
      (node (ref "T2") (pin "3") (pinfunction "3_3") (pintype "passive"))
      (node (ref "TCA1") (pin "12") (pinfunction "VDD-_12") (pintype "passive"))
      (node (ref "TCA1") (pin "13") (pinfunction "VDD-_13") (pintype "passive"))
      (node (ref "TCA1") (pin "4") (pinfunction "VDD-_4") (pintype "passive"))
      (node (ref "TCA1") (pin "5") (pinfunction "VDD-_5") (pintype "passive"))
      (node (ref "TCA1") (pin "7") (pinfunction "2IN-_7") (pintype "passive"))
      (node (ref "TCA1") (pin "8") (pinfunction "2IN+_8") (pintype "passive"))
      (node (ref "TLC1") (pin "4") (pinfunction "VDD-/GND_4") (pintype "power_in"))
      (node (ref "TPS1") (pin "11") (pinfunction "GND_11") (pintype "passive"))
      (node (ref "TPS1") (pin "3") (pinfunction "PGND_3") (pintype "passive"))
      (node (ref "TPS1") (pin "4") (pinfunction "PGND_4") (pintype "passive"))
      (node (ref "TPS1") (pin "5") (pinfunction "PGND_5") (pintype "passive"))
      (node (ref "TPS1") (pin "8") (pinfunction "SYNC_8") (pintype "passive"))
      (node (ref "USB1") (pin "10") (pinfunction "SHLD_10") (pintype "passive"))
      (node (ref "USB1") (pin "11") (pinfunction "SHLD_11") (pintype "passive"))
      (node (ref "USB1") (pin "5") (pinfunction "GND_5") (pintype "power_in"))
      (node (ref "USB1") (pin "6") (pinfunction "SHLD_6") (pintype "passive"))
      (node (ref "USB1") (pin "7") (pinfunction "SHLD_7") (pintype "passive"))
      (node (ref "USB1") (pin "8") (pinfunction "SHLD_8") (pintype "passive"))
      (node (ref "USB1") (pin "9") (pinfunction "SHLD_9") (pintype "passive"))
    )
    (net (code "42") (name "Net-(AD1-FB)") (class "Default")
      (node (ref "AD1") (pin "7") (pinfunction "FB_7") (pintype "input"))
      (node (ref "R26") (pin "2") (pinfunction "2_2") (pintype "passive"))
      (node (ref "R33") (pin "1") (pinfunction "1_1") (pintype "passive"))
    )
    (net (code "43") (name "Net-(AD1-REF)") (class "Default")
      (node (ref "AD1") (pin "6") (pinfunction "REF_6") (pintype "input"))
      (node (ref "R24") (pin "2") (pinfunction "2_2") (pintype "passive"))
    )
    (net (code "44") (name "Net-(BQ1-CHG)") (class "Default")
      (node (ref "BQ1") (pin "9") (pinfunction "CHG_9") (pintype "passive"))
      (node (ref "R11") (pin "1") (pinfunction "1_1") (pintype "passive"))
    )
    (net (code "45") (name "Net-(BQ1-DSG)") (class "Default")
      (node (ref "BQ1") (pin "7") (pinfunction "DSG_7") (pintype "passive"))
      (node (ref "R10") (pin "1") (pinfunction "1_1") (pintype "passive"))
    )
    (net (code "46") (name "Net-(BQ1-PACK)") (class "Default")
      (node (ref "BQ1") (pin "8") (pinfunction "PACK_8") (pintype "passive"))
      (node (ref "R12") (pin "1") (pinfunction "1_1") (pintype "passive"))
    )
    (net (code "47") (name "Net-(BQ1-PBI)") (class "Default")
      (node (ref "BQ1") (pin "10") (pinfunction "PBI_10") (pintype "passive"))
      (node (ref "C1") (pin "2") (pinfunction "2_2") (pintype "passive"))
    )
    (net (code "48") (name "Net-(BQ1-SRN)") (class "Default")
      (node (ref "BQ1") (pin "2") (pinfunction "SRN_2") (pintype "passive"))
      (node (ref "C3") (pin "1") (pinfunction "1_1") (pintype "passive"))
      (node (ref "R5") (pin "2") (pinfunction "2_2") (pintype "passive"))
    )
    (net (code "49") (name "Net-(BQ1-SRP)") (class "Default")
      (node (ref "BQ1") (pin "3") (pinfunction "SRP_3") (pintype "passive"))
      (node (ref "C3") (pin "2") (pinfunction "2_2") (pintype "passive"))
      (node (ref "R6") (pin "2") (pinfunction "2_2") (pintype "passive"))
    )
    (net (code "50") (name "Net-(BQ1-TS1)") (class "Default")
      (node (ref "BQ1") (pin "4") (pinfunction "TS1_4") (pintype "passive"))
      (node (ref "R3") (pin "2") (pinfunction "2_2") (pintype "passive"))
    )
    (net (code "51") (name "Net-(BQ2-BTST)") (class "Default")
      (node (ref "BQ2") (pin "21") (pinfunction "BTST_21") (pintype "power_in"))
      (node (ref "C8") (pin "1") (pinfunction "1_1") (pintype "passive"))
    )
    (net (code "52") (name "Net-(BQ2-ICHG)") (class "Default")
      (node (ref "BQ2") (pin "10") (pinfunction "ICHG_10") (pintype "input"))
      (node (ref "R9") (pin "2") (pinfunction "2_2") (pintype "passive"))
    )
    (net (code "53") (name "Net-(BQ2-ILIM)") (class "Default")
      (node (ref "BQ2") (pin "8") (pinfunction "ILIM_8") (pintype "input"))
      (node (ref "R2") (pin "2") (pinfunction "2_2") (pintype "passive"))
    )
    (net (code "54") (name "Net-(BQ2-PMID)") (class "Default")
      (node (ref "BQ2") (pin "23") (pinfunction "PMID_23") (pintype "power_in"))
      (node (ref "C6") (pin "2") (pinfunction "2_2") (pintype "passive"))
    )
    (net (code "55") (name "Net-(BQ2-REGN)") (class "Default")
      (node (ref "BQ2") (pin "22") (pinfunction "REGN_22") (pintype "power_in"))
      (node (ref "C5") (pin "2") (pinfunction "2_2") (pintype "passive"))
      (node (ref "R8") (pin "2") (pinfunction "2_2") (pintype "passive"))
    )
    (net (code "56") (name "Net-(BQ2-STAT)") (class "Default")
      (node (ref "BQ2") (pin "5") (pinfunction "STAT_5") (pintype "output"))
      (node (ref "R15") (pin "1") (pinfunction "1_1") (pintype "passive"))
    )
    (net (code "57") (name "Net-(BQ2-TS)") (class "Default")
      (node (ref "BQ2") (pin "11") (pinfunction "TS_11") (pintype "input"))
      (node (ref "R4") (pin "2") (pinfunction "2_2") (pintype "passive"))
      (node (ref "R7") (pin "1") (pinfunction "1_1") (pintype "passive"))
      (node (ref "R8") (pin "1") (pinfunction "1_1") (pintype "passive"))
    )
    (net (code "58") (name "Net-(BQ2-VAC)") (class "Default")
      (node (ref "BQ2") (pin "1") (pinfunction "VAC_1") (pintype "input"))
      (node (ref "BQ2") (pin "24") (pinfunction "VBUS_24") (pintype "power_in"))
      (node (ref "C9") (pin "2") (pinfunction "2_2") (pintype "passive"))
      (node (ref "USB1") (pin "1") (pinfunction "VBUS_1") (pintype "power_in"))
    )
    (net (code "59") (name "Net-(BQ2-~{PG})") (class "Default")
      (node (ref "BQ2") (pin "7") (pinfunction "~{PG}_7") (pintype "output"))
      (node (ref "R16") (pin "1") (pinfunction "1_1") (pintype "passive"))
    )
    (net (code "60") (name "Net-(C7-Pad2)") (class "Default")
      (node (ref "C7") (pin "2") (pinfunction "2_2") (pintype "passive"))
      (node (ref "L1") (pin "2") (pinfunction "2_2") (pintype "passive"))
    )
    (net (code "61") (name "Net-(C10-Pad2)") (class "Default")
      (node (ref "C10") (pin "2") (pinfunction "2_2") (pintype "passive"))
      (node (ref "C11") (pin "2") (pinfunction "2_2") (pintype "passive"))
    )
    (net (code "62") (name "Net-(CONNECT-PadC)") (class "Default")
      (node (ref "CONNECT") (pin "C") (pinfunction "C_C") (pintype "passive"))
      (node (ref "R47") (pin "2") (pinfunction "2_2") (pintype "passive"))
    )
    (net (code "63") (name "Net-(CSD1-D_1)") (class "Default")
      (node (ref "CSD1") (pin "5") (pinfunction "D_1_5") (pintype "passive"))
      (node (ref "CSD1") (pin "6") (pinfunction "D_2_6") (pintype "passive"))
      (node (ref "CSD1") (pin "7") (pinfunction "D_3_7") (pintype "passive"))
      (node (ref "CSD1") (pin "8") (pinfunction "D_4_8") (pintype "passive"))
      (node (ref "CSD1") (pin "9") (pinfunction "PAD_9") (pintype "passive"))
      (node (ref "CSD2") (pin "5") (pinfunction "D_1_5") (pintype "passive"))
      (node (ref "CSD2") (pin "6") (pinfunction "D_2_6") (pintype "passive"))
      (node (ref "CSD2") (pin "7") (pinfunction "D_3_7") (pintype "passive"))
      (node (ref "CSD2") (pin "8") (pinfunction "D_4_8") (pintype "passive"))
      (node (ref "CSD2") (pin "9") (pinfunction "PAD_9") (pintype "passive"))
    )
    (net (code "64") (name "Net-(CSD1-G)") (class "Default")
      (node (ref "CSD1") (pin "4") (pinfunction "G_4") (pintype "passive"))
      (node (ref "R10") (pin "2") (pinfunction "2_2") (pintype "passive"))
      (node (ref "R13") (pin "1") (pinfunction "1_1") (pintype "passive"))
    )
    (net (code "65") (name "Net-(CSD2-G)") (class "Default")
      (node (ref "CSD2") (pin "4") (pinfunction "G_4") (pintype "passive"))
      (node (ref "R11") (pin "2") (pinfunction "2_2") (pintype "passive"))
      (node (ref "R14") (pin "1") (pinfunction "1_1") (pintype "passive"))
    )
    (net (code "66") (name "Net-(D1-PadA)") (class "Default")
      (node (ref "D1") (pin "A") (pinfunction "A_A") (pintype "passive"))
      (node (ref "R42") (pin "1") (pinfunction "1_1") (pintype "passive"))
    )
    (net (code "67") (name "Net-(D2-PadA)") (class "Default")
      (node (ref "D2") (pin "A") (pinfunction "A_A") (pintype "passive"))
      (node (ref "R43") (pin "1") (pinfunction "1_1") (pintype "passive"))
    )
    (net (code "68") (name "Net-(L2-Pad2)") (class "Default")
      (node (ref "L2") (pin "2") (pinfunction "2_2") (pintype "passive"))
      (node (ref "TPS1") (pin "1") (pinfunction "SW_1") (pintype "passive"))
      (node (ref "TPS1") (pin "2") (pinfunction "SW_2") (pintype "passive"))
    )
    (net (code "69") (name "Net-(LM1-C+)") (class "Default")
      (node (ref "C17") (pin "1") (pinfunction "1_1") (pintype "passive"))
      (node (ref "LM1") (pin "5") (pinfunction "C+_5") (pintype "passive"))
    )
    (net (code "70") (name "Net-(LM1-C-)") (class "Default")
      (node (ref "C17") (pin "2") (pinfunction "2_2") (pintype "passive"))
      (node (ref "LM1") (pin "6") (pinfunction "C-_6") (pintype "passive"))
    )
    (net (code "71") (name "Net-(LOW-PadA)") (class "Default")
      (node (ref "LOW") (pin "A") (pinfunction "A_A") (pintype "passive"))
      (node (ref "R17") (pin "2") (pinfunction "2_2") (pintype "passive"))
    )
    (net (code "72") (name "Net-(PG-PadC)") (class "Default")
      (node (ref "PG") (pin "C") (pinfunction "C_C") (pintype "passive"))
      (node (ref "R16") (pin "2") (pinfunction "2_2") (pintype "passive"))
    )
    (net (code "73") (name "Net-(R15-Pad2)") (class "Default")
      (node (ref "R15") (pin "2") (pinfunction "2_2") (pintype "passive"))
      (node (ref "STAT") (pin "C") (pinfunction "C_C") (pintype "passive"))
    )
    (net (code "74") (name "Net-(R39-Pad2)") (class "Default")
      (node (ref "R39") (pin "2") (pinfunction "2_2") (pintype "passive"))
      (node (ref "ST_LINK/V1") (pin "19") (pinfunction "N/C_19") (pintype "input"))
    )
    (net (code "75") (name "Net-(R40-Pad2)") (class "Default")
      (node (ref "R40") (pin "2") (pinfunction "2_2") (pintype "passive"))
      (node (ref "ST_LINK/V1") (pin "17") (pinfunction "N/C_17") (pintype "input"))
    )
    (net (code "76") (name "Net-(R41-Pad2)") (class "Default")
      (node (ref "R41") (pin "2") (pinfunction "2_2") (pintype "passive"))
      (node (ref "ST_LINK/V1") (pin "11") (pinfunction "N/C_11") (pintype "input"))
    )
    (net (code "77") (name "Net-(R46-Pad2)") (class "Default")
      (node (ref "R46") (pin "2") (pinfunction "2_2") (pintype "passive"))
      (node (ref "STATE") (pin "C") (pinfunction "C_C") (pintype "passive"))
    )
    (net (code "78") (name "Net-(RN1-PIO2)") (class "Default")
      (node (ref "CONNECT") (pin "A") (pinfunction "A_A") (pintype "passive"))
      (node (ref "RN1") (pin "19") (pinfunction "PIO2_19") (pintype "passive"))
    )
    (net (code "79") (name "Net-(RN1-PIO4)") (class "Default")
      (node (ref "R48") (pin "2") (pinfunction "2_2") (pintype "passive"))
      (node (ref "RN1") (pin "22") (pinfunction "PIO4_22") (pintype "passive"))
    )
    (net (code "80") (name "Net-(RN1-PIO5)") (class "Default")
      (node (ref "RN1") (pin "21") (pinfunction "PIO5_21") (pintype "passive"))
      (node (ref "STATE") (pin "A") (pinfunction "A_A") (pintype "passive"))
    )
    (net (code "81") (name "Net-(STM1A-BOOT0)") (class "Default")
      (node (ref "R44") (pin "2") (pinfunction "2_2") (pintype "passive"))
      (node (ref "STM1") (pin "60") (pinfunction "BOOT0_60") (pintype "input"))
    )
    (net (code "82") (name "Net-(STM1A-PB0)") (class "Default")
      (node (ref "R42") (pin "2") (pinfunction "2_2") (pintype "passive"))
      (node (ref "STM1") (pin "26") (pinfunction "PB0_26") (pintype "bidirectional"))
    )
    (net (code "83") (name "Net-(STM1A-PB1)") (class "Default")
      (node (ref "R43") (pin "2") (pinfunction "2_2") (pintype "passive"))
      (node (ref "STM1") (pin "27") (pinfunction "PB1_27") (pintype "bidirectional"))
    )
    (net (code "84") (name "Net-(STM1A-PF0-OSC_IN(PF0))") (class "Default")
      (node (ref "C25") (pin "1") (pinfunction "1_1") (pintype "passive"))
      (node (ref "STM1") (pin "5") (pinfunction "PF0-OSC_IN(PF0)_5") (pintype "bidirectional"))
      (node (ref "X1") (pin "1") (pinfunction "OSC1_1") (pintype "passive"))
    )
    (net (code "85") (name "Net-(STM1A-PF1-OSC_OUT(PF1))") (class "Default")
      (node (ref "R45") (pin "2") (pinfunction "2_2") (pintype "passive"))
      (node (ref "STM1") (pin "6") (pinfunction "PF1-OSC_OUT(PF1)_6") (pintype "bidirectional"))
    )
    (net (code "86") (name "Net-(TLC1-1IN-)") (class "Default")
      (node (ref "R21") (pin "2") (pinfunction "2_2") (pintype "passive"))
      (node (ref "R25") (pin "1") (pinfunction "1_1") (pintype "passive"))
      (node (ref "TLC1") (pin "2") (pinfunction "1IN-_2") (pintype "input"))
    )
    (net (code "87") (name "Net-(TLC1-2IN-)") (class "Default")
      (node (ref "R22") (pin "2") (pinfunction "2_2") (pintype "passive"))
      (node (ref "R23") (pin "1") (pinfunction "1_1") (pintype "passive"))
      (node (ref "TLC1") (pin "6") (pinfunction "2IN-_6") (pintype "input"))
    )
    (net (code "88") (name "Net-(TLC2-4IN-)") (class "Default")
      (node (ref "R37") (pin "1") (pinfunction "1_1") (pintype "passive"))
      (node (ref "R38") (pin "2") (pinfunction "2_2") (pintype "passive"))
      (node (ref "TLC2") (pin "13") (pinfunction "4IN-_13") (pintype "passive"))
    )
    (net (code "89") (name "Net-(TPS1-LBI)") (class "Default")
      (node (ref "R18") (pin "2") (pinfunction "2_2") (pintype "passive"))
      (node (ref "R19") (pin "2") (pinfunction "2_2") (pintype "passive"))
      (node (ref "TPS1") (pin "7") (pinfunction "LBI_7") (pintype "passive"))
    )
    (net (code "90") (name "Net-(TPS1-LBO)") (class "Default")
      (node (ref "LOW") (pin "C") (pinfunction "C_C") (pintype "passive"))
      (node (ref "TPS1") (pin "10") (pinfunction "LBO_10") (pintype "passive"))
    )
    (net (code "91") (name "Net-(X1-OSC2)") (class "Default")
      (node (ref "C24") (pin "1") (pinfunction "1_1") (pintype "passive"))
      (node (ref "R45") (pin "1") (pinfunction "1_1") (pintype "passive"))
      (node (ref "X1") (pin "2") (pinfunction "OSC2_2") (pintype "passive"))
    )
    (net (code "92") (name "unconnected-(BQ2-NC-Pad2)") (class "Default")
      (node (ref "BQ2") (pin "2") (pinfunction "NC_2") (pintype "passive"))
    )
    (net (code "93") (name "unconnected-(DS1-OS-Pad3)") (class "Default")
      (node (ref "DS1") (pin "3") (pinfunction "OS_3") (pintype "output"))
    )
    (net (code "94") (name "unconnected-(J1-PadMP1)") (class "Default")
      (node (ref "J1") (pin "MP1") (pinfunction "MP1_MP1") (pintype "passive"))
    )
    (net (code "95") (name "unconnected-(J1-PadMP2)") (class "Default")
      (node (ref "J1") (pin "MP2") (pinfunction "MP2_MP2") (pintype "passive"))
    )
    (net (code "96") (name "unconnected-(RESET1-Pad2)") (class "Default")
      (node (ref "RESET1") (pin "2") (pinfunction "2_2") (pintype "passive"))
    )
    (net (code "97") (name "unconnected-(RESET1-Pad4)") (class "Default")
      (node (ref "RESET1") (pin "4") (pinfunction "4_4") (pintype "passive"))
    )
    (net (code "98") (name "unconnected-(RN1-AIO0-Pad30)") (class "Default")
      (node (ref "RN1") (pin "30") (pinfunction "AIO0_30") (pintype "passive"))
    )
    (net (code "99") (name "unconnected-(RN1-AIO1-Pad35)") (class "Default")
      (node (ref "RN1") (pin "35") (pinfunction "AIO1_35") (pintype "passive"))
    )
    (net (code "100") (name "unconnected-(RN1-PCMCLK-Pad7)") (class "Default")
      (node (ref "RN1") (pin "7") (pinfunction "PCMCLK_7") (pintype "passive"))
    )
    (net (code "101") (name "unconnected-(RN1-PCMIN-Pad9)") (class "Default")
      (node (ref "RN1") (pin "9") (pinfunction "PCMIN_9") (pintype "passive"))
    )
    (net (code "102") (name "unconnected-(RN1-PCMOUT-Pad10)") (class "Default")
      (node (ref "RN1") (pin "10") (pinfunction "PCMOUT_10") (pintype "passive"))
    )
    (net (code "103") (name "unconnected-(RN1-PCMSYNC-Pad8)") (class "Default")
      (node (ref "RN1") (pin "8") (pinfunction "PCMSYNC_8") (pintype "passive"))
    )
    (net (code "104") (name "unconnected-(RN1-PIO3-Pad20)") (class "Default")
      (node (ref "RN1") (pin "20") (pinfunction "PIO3_20") (pintype "passive"))
    )
    (net (code "105") (name "unconnected-(RN1-PIO6-Pad3)") (class "Default")
      (node (ref "RN1") (pin "3") (pinfunction "PIO6_3") (pintype "passive"))
    )
    (net (code "106") (name "unconnected-(RN1-PIO7-Pad4)") (class "Default")
      (node (ref "RN1") (pin "4") (pinfunction "PIO7_4") (pintype "passive"))
    )
    (net (code "107") (name "unconnected-(RN1-PIO8-Pad31)") (class "Default")
      (node (ref "RN1") (pin "31") (pinfunction "PIO8_31") (pintype "passive"))
    )
    (net (code "108") (name "unconnected-(RN1-PIO9-Pad32)") (class "Default")
      (node (ref "RN1") (pin "32") (pinfunction "PIO9_32") (pintype "passive"))
    )
    (net (code "109") (name "unconnected-(RN1-PIO10-Pad33)") (class "Default")
      (node (ref "RN1") (pin "33") (pinfunction "PIO10_33") (pintype "passive"))
    )
    (net (code "110") (name "unconnected-(RN1-PIO11-Pad34)") (class "Default")
      (node (ref "RN1") (pin "34") (pinfunction "PIO11_34") (pintype "passive"))
    )
    (net (code "111") (name "unconnected-(RN1-RESET-Pad5)") (class "Default")
      (node (ref "RN1") (pin "5") (pinfunction "RESET_5") (pintype "passive"))
    )
    (net (code "112") (name "unconnected-(RN1-SPICLK-Pad6)") (class "Default")
      (node (ref "RN1") (pin "6") (pinfunction "SPICLK_6") (pintype "passive"))
    )
    (net (code "113") (name "unconnected-(RN1-SPICSB-Pad23)") (class "Default")
      (node (ref "RN1") (pin "23") (pinfunction "SPICSB_23") (pintype "passive"))
    )
    (net (code "114") (name "unconnected-(RN1-SPIMISO-Pad24)") (class "Default")
      (node (ref "RN1") (pin "24") (pinfunction "SPIMISO_24") (pintype "passive"))
    )
    (net (code "115") (name "unconnected-(RN1-SPIMOSI-Pad2)") (class "Default")
      (node (ref "RN1") (pin "2") (pinfunction "SPIMOSI_2") (pintype "passive"))
    )
    (net (code "116") (name "unconnected-(RN1-UARTCTS-Pad16)") (class "Default")
      (node (ref "RN1") (pin "16") (pinfunction "UARTCTS_16") (pintype "passive"))
    )
    (net (code "117") (name "unconnected-(RN1-UARTRTS-Pad15)") (class "Default")
      (node (ref "RN1") (pin "15") (pinfunction "UARTRTS_15") (pintype "passive"))
    )
    (net (code "118") (name "unconnected-(RN1-USBD+-Pad17)") (class "Default")
      (node (ref "RN1") (pin "17") (pinfunction "USBD+_17") (pintype "passive"))
    )
    (net (code "119") (name "unconnected-(RN1-USBD--Pad18)") (class "Default")
      (node (ref "RN1") (pin "18") (pinfunction "USBD-_18") (pintype "passive"))
    )
    (net (code "120") (name "unconnected-(STM1A-PA1-Pad15)") (class "Default")
      (node (ref "STM1") (pin "15") (pinfunction "PA1_15") (pintype "bidirectional"))
    )
    (net (code "121") (name "unconnected-(STM1A-PA6-Pad22)") (class "Default")
      (node (ref "STM1") (pin "22") (pinfunction "PA6_22") (pintype "bidirectional"))
    )
    (net (code "122") (name "unconnected-(STM1A-PA7-Pad23)") (class "Default")
      (node (ref "STM1") (pin "23") (pinfunction "PA7_23") (pintype "bidirectional"))
    )
    (net (code "123") (name "unconnected-(STM1A-PA9-Pad42)") (class "Default")
      (node (ref "STM1") (pin "42") (pinfunction "PA9_42") (pintype "bidirectional"))
    )
    (net (code "124") (name "unconnected-(STM1A-PA10-Pad43)") (class "Default")
      (node (ref "STM1") (pin "43") (pinfunction "PA10_43") (pintype "bidirectional"))
    )
    (net (code "125") (name "unconnected-(STM1A-PA11-Pad44)") (class "Default")
      (node (ref "STM1") (pin "44") (pinfunction "PA11_44") (pintype "bidirectional"))
    )
    (net (code "126") (name "unconnected-(STM1A-PA12-Pad45)") (class "Default")
      (node (ref "STM1") (pin "45") (pinfunction "PA12_45") (pintype "bidirectional"))
    )
    (net (code "127") (name "unconnected-(STM1A-PA15-Pad50)") (class "Default")
      (node (ref "STM1") (pin "50") (pinfunction "PA15_50") (pintype "bidirectional"))
    )
    (net (code "128") (name "unconnected-(STM1A-PB2-Pad28)") (class "Default")
      (node (ref "STM1") (pin "28") (pinfunction "PB2_28") (pintype "bidirectional"))
    )
    (net (code "129") (name "unconnected-(STM1A-PB3-Pad55)") (class "Default")
      (node (ref "STM1") (pin "55") (pinfunction "PB3_55") (pintype "bidirectional"))
    )
    (net (code "130") (name "unconnected-(STM1A-PB4-Pad56)") (class "Default")
      (node (ref "STM1") (pin "56") (pinfunction "PB4_56") (pintype "bidirectional"))
    )
    (net (code "131") (name "unconnected-(STM1A-PB5-Pad57)") (class "Default")
      (node (ref "STM1") (pin "57") (pinfunction "PB5_57") (pintype "bidirectional"))
    )
    (net (code "132") (name "unconnected-(STM1A-PB6-Pad58)") (class "Default")
      (node (ref "STM1") (pin "58") (pinfunction "PB6_58") (pintype "bidirectional"))
    )
    (net (code "133") (name "unconnected-(STM1A-PB10-Pad29)") (class "Default")
      (node (ref "STM1") (pin "29") (pinfunction "PB10_29") (pintype "bidirectional"))
    )
    (net (code "134") (name "unconnected-(STM1A-PB11-Pad30)") (class "Default")
      (node (ref "STM1") (pin "30") (pinfunction "PB11_30") (pintype "bidirectional"))
    )
    (net (code "135") (name "unconnected-(STM1A-PC0-Pad8)") (class "Default")
      (node (ref "STM1") (pin "8") (pinfunction "PC0_8") (pintype "bidirectional"))
    )
    (net (code "136") (name "unconnected-(STM1A-PC1-Pad9)") (class "Default")
      (node (ref "STM1") (pin "9") (pinfunction "PC1_9") (pintype "bidirectional"))
    )
    (net (code "137") (name "unconnected-(STM1A-PC2-Pad10)") (class "Default")
      (node (ref "STM1") (pin "10") (pinfunction "PC2_10") (pintype "bidirectional"))
    )
    (net (code "138") (name "unconnected-(STM1A-PC3-Pad11)") (class "Default")
      (node (ref "STM1") (pin "11") (pinfunction "PC3_11") (pintype "bidirectional"))
    )
    (net (code "139") (name "unconnected-(STM1A-PC4-Pad24)") (class "Default")
      (node (ref "STM1") (pin "24") (pinfunction "PC4_24") (pintype "bidirectional"))
    )
    (net (code "140") (name "unconnected-(STM1A-PC5-Pad25)") (class "Default")
      (node (ref "STM1") (pin "25") (pinfunction "PC5_25") (pintype "bidirectional"))
    )
    (net (code "141") (name "unconnected-(STM1A-PC7-Pad38)") (class "Default")
      (node (ref "STM1") (pin "38") (pinfunction "PC7_38") (pintype "bidirectional"))
    )
    (net (code "142") (name "unconnected-(STM1A-PC8-Pad39)") (class "Default")
      (node (ref "STM1") (pin "39") (pinfunction "PC8_39") (pintype "bidirectional"))
    )
    (net (code "143") (name "unconnected-(STM1A-PC9-Pad40)") (class "Default")
      (node (ref "STM1") (pin "40") (pinfunction "PC9_40") (pintype "bidirectional"))
    )
    (net (code "144") (name "unconnected-(STM1A-PC12-Pad53)") (class "Default")
      (node (ref "STM1") (pin "53") (pinfunction "PC12_53") (pintype "bidirectional"))
    )
    (net (code "145") (name "unconnected-(STM1A-PC13-Pad2)") (class "Default")
      (node (ref "STM1") (pin "2") (pinfunction "PC13_2") (pintype "bidirectional"))
    )
    (net (code "146") (name "unconnected-(STM1A-PC14-OSC32_IN(PC14)-Pad3)") (class "Default")
      (node (ref "STM1") (pin "3") (pinfunction "PC14-OSC32_IN(PC14)_3") (pintype "bidirectional"))
    )
    (net (code "147") (name "unconnected-(STM1A-PC15-OSC32_OUT(PC15)-Pad4)") (class "Default")
      (node (ref "STM1") (pin "4") (pinfunction "PC15-OSC32_OUT(PC15)_4") (pintype "bidirectional"))
    )
    (net (code "148") (name "unconnected-(STM1A-PD2-Pad54)") (class "Default")
      (node (ref "STM1") (pin "54") (pinfunction "PD2_54") (pintype "bidirectional"))
    )
    (net (code "149") (name "unconnected-(SW1-Pad3)") (class "Default")
      (node (ref "SW1") (pin "3") (pinfunction "3_3") (pintype "passive"))
    )
    (net (code "150") (name "unconnected-(T1-PadMP1L)") (class "Default")
      (node (ref "T1") (pin "MP1L") (pinfunction "MP1L_MP1L") (pintype "passive"))
    )
    (net (code "151") (name "unconnected-(T1-PadMP2L)") (class "Default")
      (node (ref "T1") (pin "MP2L") (pinfunction "MP2L_MP2L") (pintype "passive"))
    )
    (net (code "152") (name "unconnected-(T1-PadMP3L)") (class "Default")
      (node (ref "T1") (pin "MP3L") (pinfunction "MP3L_MP3L") (pintype "passive"))
    )
    (net (code "153") (name "unconnected-(T1-PadMP4L)") (class "Default")
      (node (ref "T1") (pin "MP4L") (pinfunction "MP4L_MP4L") (pintype "passive"))
    )
    (net (code "154") (name "unconnected-(T2-Pad2)") (class "Default")
      (node (ref "T2") (pin "2") (pinfunction "2_2") (pintype "passive"))
    )
    (net (code "155") (name "unconnected-(T2-Pad4)") (class "Default")
      (node (ref "T2") (pin "4") (pinfunction "4_4") (pintype "passive"))
    )
    (net (code "156") (name "unconnected-(T2-Pad5)") (class "Default")
      (node (ref "T2") (pin "5") (pinfunction "5_5") (pintype "passive"))
    )
    (net (code "157") (name "unconnected-(T2-Pad6)") (class "Default")
      (node (ref "T2") (pin "6") (pinfunction "6_6") (pintype "passive"))
    )
    (net (code "158") (name "unconnected-(T2-Pad8)") (class "Default")
      (node (ref "T2") (pin "8") (pinfunction "8_8") (pintype "passive"))
    )
    (net (code "159") (name "unconnected-(T2-Pad10)") (class "Default")
      (node (ref "T2") (pin "10") (pinfunction "10_10") (pintype "passive"))
    )
    (net (code "160") (name "unconnected-(T2-Pad11)") (class "Default")
      (node (ref "T2") (pin "11") (pinfunction "11_11") (pintype "passive"))
    )
    (net (code "161") (name "unconnected-(T2-Pad12)") (class "Default")
      (node (ref "T2") (pin "12") (pinfunction "12_12") (pintype "passive"))
    )
    (net (code "162") (name "unconnected-(T2-Pad14)") (class "Default")
      (node (ref "T2") (pin "14") (pinfunction "14_14") (pintype "passive"))
    )
    (net (code "163") (name "unconnected-(T2-Pad16)") (class "Default")
      (node (ref "T2") (pin "16") (pinfunction "16_16") (pintype "passive"))
    )
    (net (code "164") (name "unconnected-(T2-Pad18)") (class "Default")
      (node (ref "T2") (pin "18") (pinfunction "18_18") (pintype "passive"))
    )
    (net (code "165") (name "unconnected-(T2-Pad19)") (class "Default")
      (node (ref "T2") (pin "19") (pinfunction "19_19") (pintype "passive"))
    )
    (net (code "166") (name "unconnected-(T2-Pad20)") (class "Default")
      (node (ref "T2") (pin "20") (pinfunction "20_20") (pintype "passive"))
    )
    (net (code "167") (name "unconnected-(T2-Pad22)") (class "Default")
      (node (ref "T2") (pin "22") (pinfunction "22_22") (pintype "passive"))
    )
    (net (code "168") (name "unconnected-(T2-Pad23)") (class "Default")
      (node (ref "T2") (pin "23") (pinfunction "23_23") (pintype "passive"))
    )
    (net (code "169") (name "unconnected-(T2-Pad24)") (class "Default")
      (node (ref "T2") (pin "24") (pinfunction "24_24") (pintype "passive"))
    )
    (net (code "170") (name "unconnected-(T2-Pad26)") (class "Default")
      (node (ref "T2") (pin "26") (pinfunction "26_26") (pintype "passive"))
    )
    (net (code "171") (name "unconnected-(T2-Pad27)") (class "Default")
      (node (ref "T2") (pin "27") (pinfunction "27_27") (pintype "passive"))
    )
    (net (code "172") (name "unconnected-(T2-Pad28)") (class "Default")
      (node (ref "T2") (pin "28") (pinfunction "28_28") (pintype "passive"))
    )
    (net (code "173") (name "unconnected-(T2-Pad30)") (class "Default")
      (node (ref "T2") (pin "30") (pinfunction "30_30") (pintype "passive"))
    )
    (net (code "174") (name "unconnected-(T2-Pad31)") (class "Default")
      (node (ref "T2") (pin "31") (pinfunction "31_31") (pintype "passive"))
    )
    (net (code "175") (name "unconnected-(T2-Pad32)") (class "Default")
      (node (ref "T2") (pin "32") (pinfunction "32_32") (pintype "passive"))
    )
    (net (code "176") (name "unconnected-(T2-Pad34)") (class "Default")
      (node (ref "T2") (pin "34") (pinfunction "34_34") (pintype "passive"))
    )
    (net (code "177") (name "unconnected-(T2-Pad35)") (class "Default")
      (node (ref "T2") (pin "35") (pinfunction "35_35") (pintype "passive"))
    )
    (net (code "178") (name "unconnected-(T2-Pad36)") (class "Default")
      (node (ref "T2") (pin "36") (pinfunction "36_36") (pintype "passive"))
    )
    (net (code "179") (name "unconnected-(T2-Pad38)") (class "Default")
      (node (ref "T2") (pin "38") (pinfunction "38_38") (pintype "passive"))
    )
    (net (code "180") (name "unconnected-(T2-Pad39)") (class "Default")
      (node (ref "T2") (pin "39") (pinfunction "39_39") (pintype "passive"))
    )
    (net (code "181") (name "unconnected-(T2-Pad40)") (class "Default")
      (node (ref "T2") (pin "40") (pinfunction "40_40") (pintype "passive"))
    )
    (net (code "182") (name "unconnected-(T2-Pad42)") (class "Default")
      (node (ref "T2") (pin "42") (pinfunction "42_42") (pintype "passive"))
    )
    (net (code "183") (name "unconnected-(T2-Pad43)") (class "Default")
      (node (ref "T2") (pin "43") (pinfunction "43_43") (pintype "passive"))
    )
    (net (code "184") (name "unconnected-(T2-Pad44)") (class "Default")
      (node (ref "T2") (pin "44") (pinfunction "44_44") (pintype "passive"))
    )
    (net (code "185") (name "unconnected-(T2-Pad46)") (class "Default")
      (node (ref "T2") (pin "46") (pinfunction "46_46") (pintype "passive"))
    )
    (net (code "186") (name "unconnected-(T2-Pad47)") (class "Default")
      (node (ref "T2") (pin "47") (pinfunction "47_47") (pintype "passive"))
    )
    (net (code "187") (name "unconnected-(T2-Pad48)") (class "Default")
      (node (ref "T2") (pin "48") (pinfunction "48_48") (pintype "passive"))
    )
    (net (code "188") (name "unconnected-(T2-Pad50)") (class "Default")
      (node (ref "T2") (pin "50") (pinfunction "50_50") (pintype "passive"))
    )
    (net (code "189") (name "unconnected-(T2-Pad52)") (class "Default")
      (node (ref "T2") (pin "52") (pinfunction "52_52") (pintype "passive"))
    )
    (net (code "190") (name "unconnected-(T2-PadMP1)") (class "Default")
      (node (ref "T2") (pin "MP1") (pinfunction "MP1_MP1") (pintype "passive"))
    )
    (net (code "191") (name "unconnected-(T2-PadMP2)") (class "Default")
      (node (ref "T2") (pin "MP2") (pinfunction "MP2_MP2") (pintype "passive"))
    )
    (net (code "192") (name "unconnected-(TCA1-2OUT-Pad2)") (class "Default")
      (node (ref "TCA1") (pin "2") (pinfunction "2OUT_2") (pintype "passive"))
    )
    (net (code "193") (name "unconnected-(TCA1-NC-Pad3)") (class "Default")
      (node (ref "TCA1") (pin "3") (pinfunction "NC_3") (pintype "passive"))
    )
    (net (code "194") (name "unconnected-(TCA1-NC-Pad6)") (class "Default")
      (node (ref "TCA1") (pin "6") (pinfunction "NC_6") (pintype "passive"))
    )
    (net (code "195") (name "unconnected-(TCA1-NC-Pad11)") (class "Default")
      (node (ref "TCA1") (pin "11") (pinfunction "NC_11") (pintype "passive"))
    )
    (net (code "196") (name "unconnected-(TCA1-NC-Pad14)") (class "Default")
      (node (ref "TCA1") (pin "14") (pinfunction "NC_14") (pintype "passive"))
    )
    (net (code "197") (name "unconnected-(TCA1-NC-Pad15)") (class "Default")
      (node (ref "TCA1") (pin "15") (pinfunction "NC_15") (pintype "passive"))
    )
    (net (code "198") (name "unconnected-(TPS1-FB-Pad12)") (class "Default")
      (node (ref "TPS1") (pin "12") (pinfunction "FB_12") (pintype "passive"))
    )
    (net (code "199") (name "unconnected-(USB1-ID-Pad4)") (class "Default")
      (node (ref "USB1") (pin "4") (pinfunction "ID_4") (pintype "passive"))
    )
  )
)
